# SCH_Wordy-Watch-V1_1_2026-04-09.net
KiCad netlist of a schematic drawn in EasyEDA
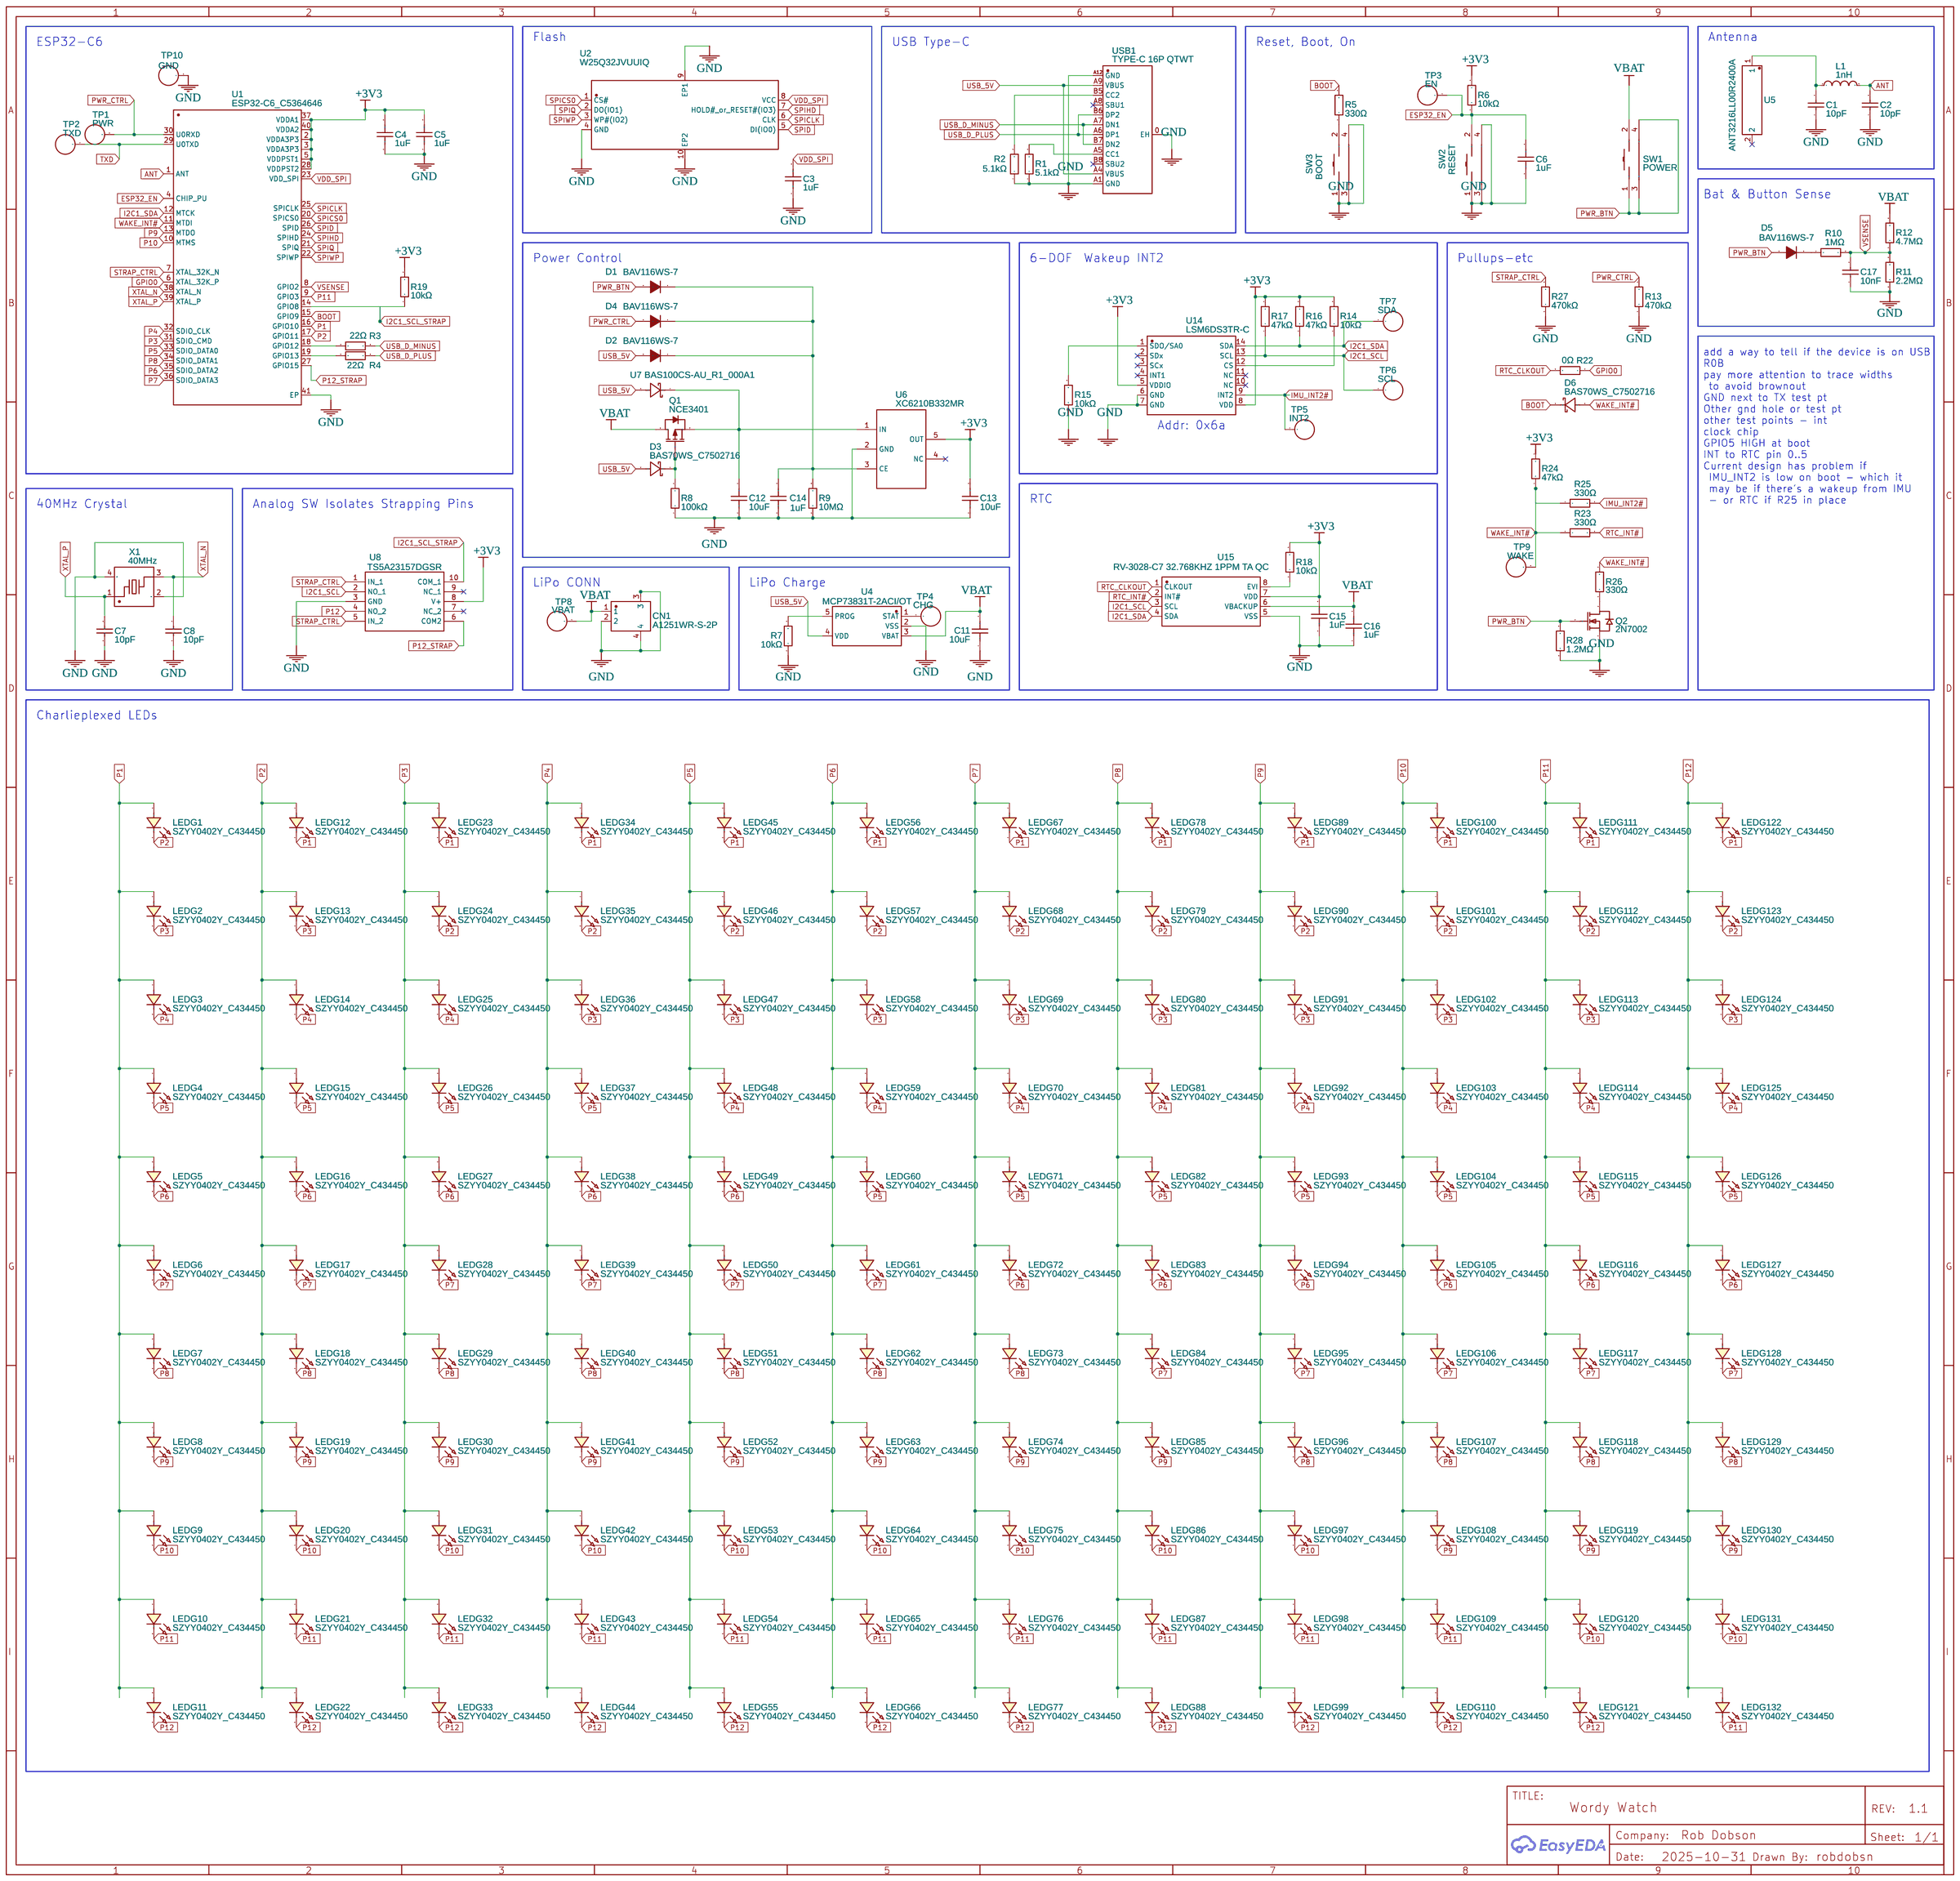
[diagram p0: schematic sheet]

(export (version "E")
  (design (tool "Eeschema 10.0.6"))
  (components
    (comp (ref "C1")
      (value "10pF")
      (fields
        (field (name "Manufacturer Part") "CL10C100JB8NNNC")
        (field (name "Manufacturer") "SAMSUNG(三星)")
      )
      (libsource (lib "") (part "CL10C100JB8NNNC"))
    )
    (comp (ref "C2")
      (value "10pF")
      (fields
        (field (name "Manufacturer Part") "CL10C100JB8NNNC")
        (field (name "Manufacturer") "SAMSUNG(三星)")
      )
      (libsource (lib "") (part "CL10C100JB8NNNC"))
    )
    (comp (ref "C3")
      (value "1uF")
      (fields
        (field (name "Manufacturer Part") "CL10A105KB8NNNC")
        (field (name "Manufacturer") "SAMSUNG(三星)")
      )
      (libsource (lib "") (part "CL10A105KB8NNNC"))
    )
    (comp (ref "C4")
      (value "1uF")
      (fields
        (field (name "Manufacturer Part") "CL10A105KB8NNNC")
        (field (name "Manufacturer") "SAMSUNG(三星)")
      )
      (libsource (lib "") (part "CL10A105KB8NNNC"))
    )
    (comp (ref "C5")
      (value "1uF")
      (fields
        (field (name "Manufacturer Part") "CL10A105KB8NNNC")
        (field (name "Manufacturer") "SAMSUNG(三星)")
      )
      (libsource (lib "") (part "CL10A105KB8NNNC"))
    )
    (comp (ref "C6")
      (value "1uF")
      (fields
        (field (name "Manufacturer Part") "CL10A105KB8NNNC")
        (field (name "Manufacturer") "SAMSUNG(三星)")
      )
      (libsource (lib "") (part "CL10A105KB8NNNC"))
    )
    (comp (ref "C7")
      (value "10pF")
      (fields
        (field (name "Manufacturer Part") "CL10C100JB8NNNC")
        (field (name "Manufacturer") "SAMSUNG(三星)")
      )
      (libsource (lib "") (part "CL10C100JB8NNNC"))
    )
    (comp (ref "C8")
      (value "10pF")
      (fields
        (field (name "Manufacturer Part") "CL10C100JB8NNNC")
        (field (name "Manufacturer") "SAMSUNG(三星)")
      )
      (libsource (lib "") (part "CL10C100JB8NNNC"))
    )
    (comp (ref "C11")
      (value "10uF")
      (fields
        (field (name "Manufacturer Part") "CL10A106MA8NRNC")
        (field (name "Manufacturer") "SAMSUNG(三星)")
      )
      (libsource (lib "") (part "CL10A106MA8NRNC"))
    )
    (comp (ref "C12")
      (value "10uF")
      (fields
        (field (name "Manufacturer Part") "CL10A106MA8NRNC")
        (field (name "Manufacturer") "SAMSUNG(三星)")
      )
      (libsource (lib "") (part "CL10A106MA8NRNC_1"))
    )
    (comp (ref "C13")
      (value "10uF")
      (fields
        (field (name "Manufacturer Part") "CL10A106MA8NRNC")
        (field (name "Manufacturer") "SAMSUNG(三星)")
      )
      (libsource (lib "") (part "CL10A106MA8NRNC_1"))
    )
    (comp (ref "C14")
      (value "1uF")
      (fields
        (field (name "Manufacturer Part") "CL10A105KB8NNNC")
        (field (name "Manufacturer") "SAMSUNG(三星)")
      )
      (libsource (lib "") (part "CL10A105KB8NNNC"))
    )
    (comp (ref "C15")
      (value "1uF")
      (fields
        (field (name "Manufacturer Part") "CL10A105KB8NNNC")
        (field (name "Manufacturer") "SAMSUNG(三星)")
      )
      (libsource (lib "") (part "CL10A105KB8NNNC"))
    )
    (comp (ref "C16")
      (value "1uF")
      (fields
        (field (name "Manufacturer Part") "CL10A105KB8NNNC")
        (field (name "Manufacturer") "SAMSUNG(三星)")
      )
      (libsource (lib "") (part "CL10A105KB8NNNC"))
    )
    (comp (ref "C17")
      (value "10nF")
      (fields (field (name "Manufacturer Part") "0603B103K500NT") (field (name "Manufacturer") "FH(风华)"))
      (libsource (lib "") (part "0603B103K500NT"))
    )
    (comp (ref "CN1")
      (value "A1251WR-S-2P")
      (fields (field (name "Manufacturer") "CJT(长江连接器)"))
      (libsource (lib "") (part "A1251WR-S-2P"))
    )
    (comp (ref "D1")
      (value "BAV116WS-7")
      (fields (field (name "Manufacturer") "DIODES(美台)"))
      (libsource (lib "") (part "BAV116WS-7"))
    )
    (comp (ref "D2")
      (value "BAV116WS-7")
      (fields (field (name "Manufacturer") "DIODES(美台)"))
      (libsource (lib "") (part "BAV116WS-7"))
    )
    (comp (ref "D3")
      (value "BAS70WS_C7502716")
      (fields (field (name "Manufacturer Part") "BAS70WS") (field (name "Manufacturer") "R+O(宏嘉诚)"))
      (libsource (lib "") (part "BAS70WS_C7502716_1"))
    )
    (comp (ref "D4")
      (value "BAV116WS-7")
      (fields (field (name "Manufacturer") "DIODES(美台)"))
      (libsource (lib "") (part "BAV116WS-7"))
    )
    (comp (ref "D5")
      (value "BAV116WS-7")
      (fields (field (name "Manufacturer") "DIODES(美台)"))
      (libsource (lib "") (part "BAV116WS-7"))
    )
    (comp (ref "D6")
      (value "BAS70WS_C7502716")
      (fields (field (name "Manufacturer Part") "BAS70WS") (field (name "Manufacturer") "R+O(宏嘉诚)"))
      (libsource (lib "") (part "BAS70WS_C7502716"))
    )
    (comp (ref "L1")
      (value "1nH")
      (fields (field (name "Manufacturer Part") "LQG15HS1N0S02D") (field (name "Manufacturer") "muRata(村田)"))
      (libsource (lib "") (part "LQG15HS1N0S02D"))
    )
    (comp (ref "LEDG1")
      (value "SZYY0402Y_C434450")
      (fields (field (name "Manufacturer Part") "SZYY0402Y") (field (name "Manufacturer") "yongyu(永裕光电)"))
      (libsource (lib "") (part "SZYY0402Y_C434450"))
    )
    (comp (ref "LEDG2")
      (value "SZYY0402Y_C434450")
      (fields (field (name "Manufacturer Part") "SZYY0402Y") (field (name "Manufacturer") "yongyu(永裕光电)"))
      (libsource (lib "") (part "SZYY0402Y_C434450"))
    )
    (comp (ref "LEDG3")
      (value "SZYY0402Y_C434450")
      (fields (field (name "Manufacturer Part") "SZYY0402Y") (field (name "Manufacturer") "yongyu(永裕光电)"))
      (libsource (lib "") (part "SZYY0402Y_C434450"))
    )
    (comp (ref "LEDG4")
      (value "SZYY0402Y_C434450")
      (fields (field (name "Manufacturer Part") "SZYY0402Y") (field (name "Manufacturer") "yongyu(永裕光电)"))
      (libsource (lib "") (part "SZYY0402Y_C434450"))
    )
    (comp (ref "LEDG5")
      (value "SZYY0402Y_C434450")
      (fields (field (name "Manufacturer Part") "SZYY0402Y") (field (name "Manufacturer") "yongyu(永裕光电)"))
      (libsource (lib "") (part "SZYY0402Y_C434450"))
    )
    (comp (ref "LEDG6")
      (value "SZYY0402Y_C434450")
      (fields (field (name "Manufacturer Part") "SZYY0402Y") (field (name "Manufacturer") "yongyu(永裕光电)"))
      (libsource (lib "") (part "SZYY0402Y_C434450"))
    )
    (comp (ref "LEDG7")
      (value "SZYY0402Y_C434450")
      (fields (field (name "Manufacturer Part") "SZYY0402Y") (field (name "Manufacturer") "yongyu(永裕光电)"))
      (libsource (lib "") (part "SZYY0402Y_C434450"))
    )
    (comp (ref "LEDG8")
      (value "SZYY0402Y_C434450")
      (fields (field (name "Manufacturer Part") "SZYY0402Y") (field (name "Manufacturer") "yongyu(永裕光电)"))
      (libsource (lib "") (part "SZYY0402Y_C434450"))
    )
    (comp (ref "LEDG9")
      (value "SZYY0402Y_C434450")
      (fields (field (name "Manufacturer Part") "SZYY0402Y") (field (name "Manufacturer") "yongyu(永裕光电)"))
      (libsource (lib "") (part "SZYY0402Y_C434450"))
    )
    (comp (ref "LEDG10")
      (value "SZYY0402Y_C434450")
      (fields (field (name "Manufacturer Part") "SZYY0402Y") (field (name "Manufacturer") "yongyu(永裕光电)"))
      (libsource (lib "") (part "SZYY0402Y_C434450"))
    )
    (comp (ref "LEDG11")
      (value "SZYY0402Y_C434450")
      (fields (field (name "Manufacturer Part") "SZYY0402Y") (field (name "Manufacturer") "yongyu(永裕光电)"))
      (libsource (lib "") (part "SZYY0402Y_C434450"))
    )
    (comp (ref "LEDG12")
      (value "SZYY0402Y_C434450")
      (fields (field (name "Manufacturer Part") "SZYY0402Y") (field (name "Manufacturer") "yongyu(永裕光电)"))
      (libsource (lib "") (part "SZYY0402Y_C434450"))
    )
    (comp (ref "LEDG13")
      (value "SZYY0402Y_C434450")
      (fields (field (name "Manufacturer Part") "SZYY0402Y") (field (name "Manufacturer") "yongyu(永裕光电)"))
      (libsource (lib "") (part "SZYY0402Y_C434450"))
    )
    (comp (ref "LEDG14")
      (value "SZYY0402Y_C434450")
      (fields (field (name "Manufacturer Part") "SZYY0402Y") (field (name "Manufacturer") "yongyu(永裕光电)"))
      (libsource (lib "") (part "SZYY0402Y_C434450"))
    )
    (comp (ref "LEDG15")
      (value "SZYY0402Y_C434450")
      (fields (field (name "Manufacturer Part") "SZYY0402Y") (field (name "Manufacturer") "yongyu(永裕光电)"))
      (libsource (lib "") (part "SZYY0402Y_C434450"))
    )
    (comp (ref "LEDG16")
      (value "SZYY0402Y_C434450")
      (fields (field (name "Manufacturer Part") "SZYY0402Y") (field (name "Manufacturer") "yongyu(永裕光电)"))
      (libsource (lib "") (part "SZYY0402Y_C434450"))
    )
    (comp (ref "LEDG17")
      (value "SZYY0402Y_C434450")
      (fields (field (name "Manufacturer Part") "SZYY0402Y") (field (name "Manufacturer") "yongyu(永裕光电)"))
      (libsource (lib "") (part "SZYY0402Y_C434450"))
    )
    (comp (ref "LEDG18")
      (value "SZYY0402Y_C434450")
      (fields (field (name "Manufacturer Part") "SZYY0402Y") (field (name "Manufacturer") "yongyu(永裕光电)"))
      (libsource (lib "") (part "SZYY0402Y_C434450"))
    )
    (comp (ref "LEDG19")
      (value "SZYY0402Y_C434450")
      (fields (field (name "Manufacturer Part") "SZYY0402Y") (field (name "Manufacturer") "yongyu(永裕光电)"))
      (libsource (lib "") (part "SZYY0402Y_C434450"))
    )
    (comp (ref "LEDG20")
      (value "SZYY0402Y_C434450")
      (fields (field (name "Manufacturer Part") "SZYY0402Y") (field (name "Manufacturer") "yongyu(永裕光电)"))
      (libsource (lib "") (part "SZYY0402Y_C434450"))
    )
    (comp (ref "LEDG21")
      (value "SZYY0402Y_C434450")
      (fields (field (name "Manufacturer Part") "SZYY0402Y") (field (name "Manufacturer") "yongyu(永裕光电)"))
      (libsource (lib "") (part "SZYY0402Y_C434450"))
    )
    (comp (ref "LEDG22")
      (value "SZYY0402Y_C434450")
      (fields (field (name "Manufacturer Part") "SZYY0402Y") (field (name "Manufacturer") "yongyu(永裕光电)"))
      (libsource (lib "") (part "SZYY0402Y_C434450"))
    )
    (comp (ref "LEDG23")
      (value "SZYY0402Y_C434450")
      (fields (field (name "Manufacturer Part") "SZYY0402Y") (field (name "Manufacturer") "yongyu(永裕光电)"))
      (libsource (lib "") (part "SZYY0402Y_C434450"))
    )
    (comp (ref "LEDG24")
      (value "SZYY0402Y_C434450")
      (fields (field (name "Manufacturer Part") "SZYY0402Y") (field (name "Manufacturer") "yongyu(永裕光电)"))
      (libsource (lib "") (part "SZYY0402Y_C434450"))
    )
    (comp (ref "LEDG25")
      (value "SZYY0402Y_C434450")
      (fields (field (name "Manufacturer Part") "SZYY0402Y") (field (name "Manufacturer") "yongyu(永裕光电)"))
      (libsource (lib "") (part "SZYY0402Y_C434450"))
    )
    (comp (ref "LEDG26")
      (value "SZYY0402Y_C434450")
      (fields (field (name "Manufacturer Part") "SZYY0402Y") (field (name "Manufacturer") "yongyu(永裕光电)"))
      (libsource (lib "") (part "SZYY0402Y_C434450"))
    )
    (comp (ref "LEDG27")
      (value "SZYY0402Y_C434450")
      (fields (field (name "Manufacturer Part") "SZYY0402Y") (field (name "Manufacturer") "yongyu(永裕光电)"))
      (libsource (lib "") (part "SZYY0402Y_C434450"))
    )
    (comp (ref "LEDG28")
      (value "SZYY0402Y_C434450")
      (fields (field (name "Manufacturer Part") "SZYY0402Y") (field (name "Manufacturer") "yongyu(永裕光电)"))
      (libsource (lib "") (part "SZYY0402Y_C434450"))
    )
    (comp (ref "LEDG29")
      (value "SZYY0402Y_C434450")
      (fields (field (name "Manufacturer Part") "SZYY0402Y") (field (name "Manufacturer") "yongyu(永裕光电)"))
      (libsource (lib "") (part "SZYY0402Y_C434450"))
    )
    (comp (ref "LEDG30")
      (value "SZYY0402Y_C434450")
      (fields (field (name "Manufacturer Part") "SZYY0402Y") (field (name "Manufacturer") "yongyu(永裕光电)"))
      (libsource (lib "") (part "SZYY0402Y_C434450"))
    )
    (comp (ref "LEDG31")
      (value "SZYY0402Y_C434450")
      (fields (field (name "Manufacturer Part") "SZYY0402Y") (field (name "Manufacturer") "yongyu(永裕光电)"))
      (libsource (lib "") (part "SZYY0402Y_C434450"))
    )
    (comp (ref "LEDG32")
      (value "SZYY0402Y_C434450")
      (fields (field (name "Manufacturer Part") "SZYY0402Y") (field (name "Manufacturer") "yongyu(永裕光电)"))
      (libsource (lib "") (part "SZYY0402Y_C434450"))
    )
    (comp (ref "LEDG33")
      (value "SZYY0402Y_C434450")
      (fields (field (name "Manufacturer Part") "SZYY0402Y") (field (name "Manufacturer") "yongyu(永裕光电)"))
      (libsource (lib "") (part "SZYY0402Y_C434450"))
    )
    (comp (ref "LEDG34")
      (value "SZYY0402Y_C434450")
      (fields (field (name "Manufacturer Part") "SZYY0402Y") (field (name "Manufacturer") "yongyu(永裕光电)"))
      (libsource (lib "") (part "SZYY0402Y_C434450"))
    )
    (comp (ref "LEDG35")
      (value "SZYY0402Y_C434450")
      (fields (field (name "Manufacturer Part") "SZYY0402Y") (field (name "Manufacturer") "yongyu(永裕光电)"))
      (libsource (lib "") (part "SZYY0402Y_C434450"))
    )
    (comp (ref "LEDG36")
      (value "SZYY0402Y_C434450")
      (fields (field (name "Manufacturer Part") "SZYY0402Y") (field (name "Manufacturer") "yongyu(永裕光电)"))
      (libsource (lib "") (part "SZYY0402Y_C434450"))
    )
    (comp (ref "LEDG37")
      (value "SZYY0402Y_C434450")
      (fields (field (name "Manufacturer Part") "SZYY0402Y") (field (name "Manufacturer") "yongyu(永裕光电)"))
      (libsource (lib "") (part "SZYY0402Y_C434450"))
    )
    (comp (ref "LEDG38")
      (value "SZYY0402Y_C434450")
      (fields (field (name "Manufacturer Part") "SZYY0402Y") (field (name "Manufacturer") "yongyu(永裕光电)"))
      (libsource (lib "") (part "SZYY0402Y_C434450"))
    )
    (comp (ref "LEDG39")
      (value "SZYY0402Y_C434450")
      (fields (field (name "Manufacturer Part") "SZYY0402Y") (field (name "Manufacturer") "yongyu(永裕光电)"))
      (libsource (lib "") (part "SZYY0402Y_C434450"))
    )
    (comp (ref "LEDG40")
      (value "SZYY0402Y_C434450")
      (fields (field (name "Manufacturer Part") "SZYY0402Y") (field (name "Manufacturer") "yongyu(永裕光电)"))
      (libsource (lib "") (part "SZYY0402Y_C434450"))
    )
    (comp (ref "LEDG41")
      (value "SZYY0402Y_C434450")
      (fields (field (name "Manufacturer Part") "SZYY0402Y") (field (name "Manufacturer") "yongyu(永裕光电)"))
      (libsource (lib "") (part "SZYY0402Y_C434450"))
    )
    (comp (ref "LEDG42")
      (value "SZYY0402Y_C434450")
      (fields (field (name "Manufacturer Part") "SZYY0402Y") (field (name "Manufacturer") "yongyu(永裕光电)"))
      (libsource (lib "") (part "SZYY0402Y_C434450"))
    )
    (comp (ref "LEDG43")
      (value "SZYY0402Y_C434450")
      (fields (field (name "Manufacturer Part") "SZYY0402Y") (field (name "Manufacturer") "yongyu(永裕光电)"))
      (libsource (lib "") (part "SZYY0402Y_C434450"))
    )
    (comp (ref "LEDG44")
      (value "SZYY0402Y_C434450")
      (fields (field (name "Manufacturer Part") "SZYY0402Y") (field (name "Manufacturer") "yongyu(永裕光电)"))
      (libsource (lib "") (part "SZYY0402Y_C434450"))
    )
    (comp (ref "LEDG45")
      (value "SZYY0402Y_C434450")
      (fields (field (name "Manufacturer Part") "SZYY0402Y") (field (name "Manufacturer") "yongyu(永裕光电)"))
      (libsource (lib "") (part "SZYY0402Y_C434450"))
    )
    (comp (ref "LEDG46")
      (value "SZYY0402Y_C434450")
      (fields (field (name "Manufacturer Part") "SZYY0402Y") (field (name "Manufacturer") "yongyu(永裕光电)"))
      (libsource (lib "") (part "SZYY0402Y_C434450"))
    )
    (comp (ref "LEDG47")
      (value "SZYY0402Y_C434450")
      (fields (field (name "Manufacturer Part") "SZYY0402Y") (field (name "Manufacturer") "yongyu(永裕光电)"))
      (libsource (lib "") (part "SZYY0402Y_C434450"))
    )
    (comp (ref "LEDG48")
      (value "SZYY0402Y_C434450")
      (fields (field (name "Manufacturer Part") "SZYY0402Y") (field (name "Manufacturer") "yongyu(永裕光电)"))
      (libsource (lib "") (part "SZYY0402Y_C434450"))
    )
    (comp (ref "LEDG49")
      (value "SZYY0402Y_C434450")
      (fields (field (name "Manufacturer Part") "SZYY0402Y") (field (name "Manufacturer") "yongyu(永裕光电)"))
      (libsource (lib "") (part "SZYY0402Y_C434450"))
    )
    (comp (ref "LEDG50")
      (value "SZYY0402Y_C434450")
      (fields (field (name "Manufacturer Part") "SZYY0402Y") (field (name "Manufacturer") "yongyu(永裕光电)"))
      (libsource (lib "") (part "SZYY0402Y_C434450"))
    )
    (comp (ref "LEDG51")
      (value "SZYY0402Y_C434450")
      (fields (field (name "Manufacturer Part") "SZYY0402Y") (field (name "Manufacturer") "yongyu(永裕光电)"))
      (libsource (lib "") (part "SZYY0402Y_C434450"))
    )
    (comp (ref "LEDG52")
      (value "SZYY0402Y_C434450")
      (fields (field (name "Manufacturer Part") "SZYY0402Y") (field (name "Manufacturer") "yongyu(永裕光电)"))
      (libsource (lib "") (part "SZYY0402Y_C434450"))
    )
    (comp (ref "LEDG53")
      (value "SZYY0402Y_C434450")
      (fields (field (name "Manufacturer Part") "SZYY0402Y") (field (name "Manufacturer") "yongyu(永裕光电)"))
      (libsource (lib "") (part "SZYY0402Y_C434450"))
    )
    (comp (ref "LEDG54")
      (value "SZYY0402Y_C434450")
      (fields (field (name "Manufacturer Part") "SZYY0402Y") (field (name "Manufacturer") "yongyu(永裕光电)"))
      (libsource (lib "") (part "SZYY0402Y_C434450"))
    )
    (comp (ref "LEDG55")
      (value "SZYY0402Y_C434450")
      (fields (field (name "Manufacturer Part") "SZYY0402Y") (field (name "Manufacturer") "yongyu(永裕光电)"))
      (libsource (lib "") (part "SZYY0402Y_C434450"))
    )
    (comp (ref "LEDG56")
      (value "SZYY0402Y_C434450")
      (fields (field (name "Manufacturer Part") "SZYY0402Y") (field (name "Manufacturer") "yongyu(永裕光电)"))
      (libsource (lib "") (part "SZYY0402Y_C434450"))
    )
    (comp (ref "LEDG57")
      (value "SZYY0402Y_C434450")
      (fields (field (name "Manufacturer Part") "SZYY0402Y") (field (name "Manufacturer") "yongyu(永裕光电)"))
      (libsource (lib "") (part "SZYY0402Y_C434450"))
    )
    (comp (ref "LEDG58")
      (value "SZYY0402Y_C434450")
      (fields (field (name "Manufacturer Part") "SZYY0402Y") (field (name "Manufacturer") "yongyu(永裕光电)"))
      (libsource (lib "") (part "SZYY0402Y_C434450"))
    )
    (comp (ref "LEDG59")
      (value "SZYY0402Y_C434450")
      (fields (field (name "Manufacturer Part") "SZYY0402Y") (field (name "Manufacturer") "yongyu(永裕光电)"))
      (libsource (lib "") (part "SZYY0402Y_C434450"))
    )
    (comp (ref "LEDG60")
      (value "SZYY0402Y_C434450")
      (fields (field (name "Manufacturer Part") "SZYY0402Y") (field (name "Manufacturer") "yongyu(永裕光电)"))
      (libsource (lib "") (part "SZYY0402Y_C434450"))
    )
    (comp (ref "LEDG61")
      (value "SZYY0402Y_C434450")
      (fields (field (name "Manufacturer Part") "SZYY0402Y") (field (name "Manufacturer") "yongyu(永裕光电)"))
      (libsource (lib "") (part "SZYY0402Y_C434450"))
    )
    (comp (ref "LEDG62")
      (value "SZYY0402Y_C434450")
      (fields (field (name "Manufacturer Part") "SZYY0402Y") (field (name "Manufacturer") "yongyu(永裕光电)"))
      (libsource (lib "") (part "SZYY0402Y_C434450"))
    )
    (comp (ref "LEDG63")
      (value "SZYY0402Y_C434450")
      (fields (field (name "Manufacturer Part") "SZYY0402Y") (field (name "Manufacturer") "yongyu(永裕光电)"))
      (libsource (lib "") (part "SZYY0402Y_C434450"))
    )
    (comp (ref "LEDG64")
      (value "SZYY0402Y_C434450")
      (fields (field (name "Manufacturer Part") "SZYY0402Y") (field (name "Manufacturer") "yongyu(永裕光电)"))
      (libsource (lib "") (part "SZYY0402Y_C434450"))
    )
    (comp (ref "LEDG65")
      (value "SZYY0402Y_C434450")
      (fields (field (name "Manufacturer Part") "SZYY0402Y") (field (name "Manufacturer") "yongyu(永裕光电)"))
      (libsource (lib "") (part "SZYY0402Y_C434450"))
    )
    (comp (ref "LEDG66")
      (value "SZYY0402Y_C434450")
      (fields (field (name "Manufacturer Part") "SZYY0402Y") (field (name "Manufacturer") "yongyu(永裕光电)"))
      (libsource (lib "") (part "SZYY0402Y_C434450"))
    )
    (comp (ref "LEDG67")
      (value "SZYY0402Y_C434450")
      (fields (field (name "Manufacturer Part") "SZYY0402Y") (field (name "Manufacturer") "yongyu(永裕光电)"))
      (libsource (lib "") (part "SZYY0402Y_C434450"))
    )
    (comp (ref "LEDG68")
      (value "SZYY0402Y_C434450")
      (fields (field (name "Manufacturer Part") "SZYY0402Y") (field (name "Manufacturer") "yongyu(永裕光电)"))
      (libsource (lib "") (part "SZYY0402Y_C434450"))
    )
    (comp (ref "LEDG69")
      (value "SZYY0402Y_C434450")
      (fields (field (name "Manufacturer Part") "SZYY0402Y") (field (name "Manufacturer") "yongyu(永裕光电)"))
      (libsource (lib "") (part "SZYY0402Y_C434450"))
    )
    (comp (ref "LEDG70")
      (value "SZYY0402Y_C434450")
      (fields (field (name "Manufacturer Part") "SZYY0402Y") (field (name "Manufacturer") "yongyu(永裕光电)"))
      (libsource (lib "") (part "SZYY0402Y_C434450"))
    )
    (comp (ref "LEDG71")
      (value "SZYY0402Y_C434450")
      (fields (field (name "Manufacturer Part") "SZYY0402Y") (field (name "Manufacturer") "yongyu(永裕光电)"))
      (libsource (lib "") (part "SZYY0402Y_C434450"))
    )
    (comp (ref "LEDG72")
      (value "SZYY0402Y_C434450")
      (fields (field (name "Manufacturer Part") "SZYY0402Y") (field (name "Manufacturer") "yongyu(永裕光电)"))
      (libsource (lib "") (part "SZYY0402Y_C434450"))
    )
    (comp (ref "LEDG73")
      (value "SZYY0402Y_C434450")
      (fields (field (name "Manufacturer Part") "SZYY0402Y") (field (name "Manufacturer") "yongyu(永裕光电)"))
      (libsource (lib "") (part "SZYY0402Y_C434450"))
    )
    (comp (ref "LEDG74")
      (value "SZYY0402Y_C434450")
      (fields (field (name "Manufacturer Part") "SZYY0402Y") (field (name "Manufacturer") "yongyu(永裕光电)"))
      (libsource (lib "") (part "SZYY0402Y_C434450"))
    )
    (comp (ref "LEDG75")
      (value "SZYY0402Y_C434450")
      (fields (field (name "Manufacturer Part") "SZYY0402Y") (field (name "Manufacturer") "yongyu(永裕光电)"))
      (libsource (lib "") (part "SZYY0402Y_C434450"))
    )
    (comp (ref "LEDG76")
      (value "SZYY0402Y_C434450")
      (fields (field (name "Manufacturer Part") "SZYY0402Y") (field (name "Manufacturer") "yongyu(永裕光电)"))
      (libsource (lib "") (part "SZYY0402Y_C434450"))
    )
    (comp (ref "LEDG77")
      (value "SZYY0402Y_C434450")
      (fields (field (name "Manufacturer Part") "SZYY0402Y") (field (name "Manufacturer") "yongyu(永裕光电)"))
      (libsource (lib "") (part "SZYY0402Y_C434450"))
    )
    (comp (ref "LEDG78")
      (value "SZYY0402Y_C434450")
      (fields (field (name "Manufacturer Part") "SZYY0402Y") (field (name "Manufacturer") "yongyu(永裕光电)"))
      (libsource (lib "") (part "SZYY0402Y_C434450"))
    )
    (comp (ref "LEDG79")
      (value "SZYY0402Y_C434450")
      (fields (field (name "Manufacturer Part") "SZYY0402Y") (field (name "Manufacturer") "yongyu(永裕光电)"))
      (libsource (lib "") (part "SZYY0402Y_C434450"))
    )
    (comp (ref "LEDG80")
      (value "SZYY0402Y_C434450")
      (fields (field (name "Manufacturer Part") "SZYY0402Y") (field (name "Manufacturer") "yongyu(永裕光电)"))
      (libsource (lib "") (part "SZYY0402Y_C434450"))
    )
    (comp (ref "LEDG81")
      (value "SZYY0402Y_C434450")
      (fields (field (name "Manufacturer Part") "SZYY0402Y") (field (name "Manufacturer") "yongyu(永裕光电)"))
      (libsource (lib "") (part "SZYY0402Y_C434450"))
    )
    (comp (ref "LEDG82")
      (value "SZYY0402Y_C434450")
      (fields (field (name "Manufacturer Part") "SZYY0402Y") (field (name "Manufacturer") "yongyu(永裕光电)"))
      (libsource (lib "") (part "SZYY0402Y_C434450"))
    )
    (comp (ref "LEDG83")
      (value "SZYY0402Y_C434450")
      (fields (field (name "Manufacturer Part") "SZYY0402Y") (field (name "Manufacturer") "yongyu(永裕光电)"))
      (libsource (lib "") (part "SZYY0402Y_C434450"))
    )
    (comp (ref "LEDG84")
      (value "SZYY0402Y_C434450")
      (fields (field (name "Manufacturer Part") "SZYY0402Y") (field (name "Manufacturer") "yongyu(永裕光电)"))
      (libsource (lib "") (part "SZYY0402Y_C434450"))
    )
    (comp (ref "LEDG85")
      (value "SZYY0402Y_C434450")
      (fields (field (name "Manufacturer Part") "SZYY0402Y") (field (name "Manufacturer") "yongyu(永裕光电)"))
      (libsource (lib "") (part "SZYY0402Y_C434450"))
    )
    (comp (ref "LEDG86")
      (value "SZYY0402Y_C434450")
      (fields (field (name "Manufacturer Part") "SZYY0402Y") (field (name "Manufacturer") "yongyu(永裕光电)"))
      (libsource (lib "") (part "SZYY0402Y_C434450"))
    )
    (comp (ref "LEDG87")
      (value "SZYY0402Y_C434450")
      (fields (field (name "Manufacturer Part") "SZYY0402Y") (field (name "Manufacturer") "yongyu(永裕光电)"))
      (libsource (lib "") (part "SZYY0402Y_C434450"))
    )
    (comp (ref "LEDG88")
      (value "SZYY0402Y_C434450")
      (fields (field (name "Manufacturer Part") "SZYY0402Y") (field (name "Manufacturer") "yongyu(永裕光电)"))
      (libsource (lib "") (part "SZYY0402Y_C434450"))
    )
    (comp (ref "LEDG89")
      (value "SZYY0402Y_C434450")
      (fields (field (name "Manufacturer Part") "SZYY0402Y") (field (name "Manufacturer") "yongyu(永裕光电)"))
      (libsource (lib "") (part "SZYY0402Y_C434450"))
    )
    (comp (ref "LEDG90")
      (value "SZYY0402Y_C434450")
      (fields (field (name "Manufacturer Part") "SZYY0402Y") (field (name "Manufacturer") "yongyu(永裕光电)"))
      (libsource (lib "") (part "SZYY0402Y_C434450"))
    )
    (comp (ref "LEDG91")
      (value "SZYY0402Y_C434450")
      (fields (field (name "Manufacturer Part") "SZYY0402Y") (field (name "Manufacturer") "yongyu(永裕光电)"))
      (libsource (lib "") (part "SZYY0402Y_C434450"))
    )
    (comp (ref "LEDG92")
      (value "SZYY0402Y_C434450")
      (fields (field (name "Manufacturer Part") "SZYY0402Y") (field (name "Manufacturer") "yongyu(永裕光电)"))
      (libsource (lib "") (part "SZYY0402Y_C434450"))
    )
    (comp (ref "LEDG93")
      (value "SZYY0402Y_C434450")
      (fields (field (name "Manufacturer Part") "SZYY0402Y") (field (name "Manufacturer") "yongyu(永裕光电)"))
      (libsource (lib "") (part "SZYY0402Y_C434450"))
    )
    (comp (ref "LEDG94")
      (value "SZYY0402Y_C434450")
      (fields (field (name "Manufacturer Part") "SZYY0402Y") (field (name "Manufacturer") "yongyu(永裕光电)"))
      (libsource (lib "") (part "SZYY0402Y_C434450"))
    )
    (comp (ref "LEDG95")
      (value "SZYY0402Y_C434450")
      (fields (field (name "Manufacturer Part") "SZYY0402Y") (field (name "Manufacturer") "yongyu(永裕光电)"))
      (libsource (lib "") (part "SZYY0402Y_C434450"))
    )
    (comp (ref "LEDG96")
      (value "SZYY0402Y_C434450")
      (fields (field (name "Manufacturer Part") "SZYY0402Y") (field (name "Manufacturer") "yongyu(永裕光电)"))
      (libsource (lib "") (part "SZYY0402Y_C434450"))
    )
    (comp (ref "LEDG97")
      (value "SZYY0402Y_C434450")
      (fields (field (name "Manufacturer Part") "SZYY0402Y") (field (name "Manufacturer") "yongyu(永裕光电)"))
      (libsource (lib "") (part "SZYY0402Y_C434450"))
    )
    (comp (ref "LEDG98")
      (value "SZYY0402Y_C434450")
      (fields (field (name "Manufacturer Part") "SZYY0402Y") (field (name "Manufacturer") "yongyu(永裕光电)"))
      (libsource (lib "") (part "SZYY0402Y_C434450"))
    )
    (comp (ref "LEDG99")
      (value "SZYY0402Y_C434450")
      (fields (field (name "Manufacturer Part") "SZYY0402Y") (field (name "Manufacturer") "yongyu(永裕光电)"))
      (libsource (lib "") (part "SZYY0402Y_C434450"))
    )
    (comp (ref "LEDG100")
      (value "SZYY0402Y_C434450")
      (fields (field (name "Manufacturer Part") "SZYY0402Y") (field (name "Manufacturer") "yongyu(永裕光电)"))
      (libsource (lib "") (part "SZYY0402Y_C434450"))
    )
    (comp (ref "LEDG101")
      (value "SZYY0402Y_C434450")
      (fields (field (name "Manufacturer Part") "SZYY0402Y") (field (name "Manufacturer") "yongyu(永裕光电)"))
      (libsource (lib "") (part "SZYY0402Y_C434450"))
    )
    (comp (ref "LEDG102")
      (value "SZYY0402Y_C434450")
      (fields (field (name "Manufacturer Part") "SZYY0402Y") (field (name "Manufacturer") "yongyu(永裕光电)"))
      (libsource (lib "") (part "SZYY0402Y_C434450"))
    )
    (comp (ref "LEDG103")
      (value "SZYY0402Y_C434450")
      (fields (field (name "Manufacturer Part") "SZYY0402Y") (field (name "Manufacturer") "yongyu(永裕光电)"))
      (libsource (lib "") (part "SZYY0402Y_C434450"))
    )
    (comp (ref "LEDG104")
      (value "SZYY0402Y_C434450")
      (fields (field (name "Manufacturer Part") "SZYY0402Y") (field (name "Manufacturer") "yongyu(永裕光电)"))
      (libsource (lib "") (part "SZYY0402Y_C434450"))
    )
    (comp (ref "LEDG105")
      (value "SZYY0402Y_C434450")
      (fields (field (name "Manufacturer Part") "SZYY0402Y") (field (name "Manufacturer") "yongyu(永裕光电)"))
      (libsource (lib "") (part "SZYY0402Y_C434450"))
    )
    (comp (ref "LEDG106")
      (value "SZYY0402Y_C434450")
      (fields (field (name "Manufacturer Part") "SZYY0402Y") (field (name "Manufacturer") "yongyu(永裕光电)"))
      (libsource (lib "") (part "SZYY0402Y_C434450"))
    )
    (comp (ref "LEDG107")
      (value "SZYY0402Y_C434450")
      (fields (field (name "Manufacturer Part") "SZYY0402Y") (field (name "Manufacturer") "yongyu(永裕光电)"))
      (libsource (lib "") (part "SZYY0402Y_C434450"))
    )
    (comp (ref "LEDG108")
      (value "SZYY0402Y_C434450")
      (fields (field (name "Manufacturer Part") "SZYY0402Y") (field (name "Manufacturer") "yongyu(永裕光电)"))
      (libsource (lib "") (part "SZYY0402Y_C434450"))
    )
    (comp (ref "LEDG109")
      (value "SZYY0402Y_C434450")
      (fields (field (name "Manufacturer Part") "SZYY0402Y") (field (name "Manufacturer") "yongyu(永裕光电)"))
      (libsource (lib "") (part "SZYY0402Y_C434450"))
    )
    (comp (ref "LEDG110")
      (value "SZYY0402Y_C434450")
      (fields (field (name "Manufacturer Part") "SZYY0402Y") (field (name "Manufacturer") "yongyu(永裕光电)"))
      (libsource (lib "") (part "SZYY0402Y_C434450"))
    )
    (comp (ref "LEDG111")
      (value "SZYY0402Y_C434450")
      (fields (field (name "Manufacturer Part") "SZYY0402Y") (field (name "Manufacturer") "yongyu(永裕光电)"))
      (libsource (lib "") (part "SZYY0402Y_C434450"))
    )
    (comp (ref "LEDG112")
      (value "SZYY0402Y_C434450")
      (fields (field (name "Manufacturer Part") "SZYY0402Y") (field (name "Manufacturer") "yongyu(永裕光电)"))
      (libsource (lib "") (part "SZYY0402Y_C434450"))
    )
    (comp (ref "LEDG113")
      (value "SZYY0402Y_C434450")
      (fields (field (name "Manufacturer Part") "SZYY0402Y") (field (name "Manufacturer") "yongyu(永裕光电)"))
      (libsource (lib "") (part "SZYY0402Y_C434450"))
    )
    (comp (ref "LEDG114")
      (value "SZYY0402Y_C434450")
      (fields (field (name "Manufacturer Part") "SZYY0402Y") (field (name "Manufacturer") "yongyu(永裕光电)"))
      (libsource (lib "") (part "SZYY0402Y_C434450"))
    )
    (comp (ref "LEDG115")
      (value "SZYY0402Y_C434450")
      (fields (field (name "Manufacturer Part") "SZYY0402Y") (field (name "Manufacturer") "yongyu(永裕光电)"))
      (libsource (lib "") (part "SZYY0402Y_C434450"))
    )
    (comp (ref "LEDG116")
      (value "SZYY0402Y_C434450")
      (fields (field (name "Manufacturer Part") "SZYY0402Y") (field (name "Manufacturer") "yongyu(永裕光电)"))
      (libsource (lib "") (part "SZYY0402Y_C434450"))
    )
    (comp (ref "LEDG117")
      (value "SZYY0402Y_C434450")
      (fields (field (name "Manufacturer Part") "SZYY0402Y") (field (name "Manufacturer") "yongyu(永裕光电)"))
      (libsource (lib "") (part "SZYY0402Y_C434450"))
    )
    (comp (ref "LEDG118")
      (value "SZYY0402Y_C434450")
      (fields (field (name "Manufacturer Part") "SZYY0402Y") (field (name "Manufacturer") "yongyu(永裕光电)"))
      (libsource (lib "") (part "SZYY0402Y_C434450"))
    )
    (comp (ref "LEDG119")
      (value "SZYY0402Y_C434450")
      (fields (field (name "Manufacturer Part") "SZYY0402Y") (field (name "Manufacturer") "yongyu(永裕光电)"))
      (libsource (lib "") (part "SZYY0402Y_C434450"))
    )
    (comp (ref "LEDG120")
      (value "SZYY0402Y_C434450")
      (fields (field (name "Manufacturer Part") "SZYY0402Y") (field (name "Manufacturer") "yongyu(永裕光电)"))
      (libsource (lib "") (part "SZYY0402Y_C434450"))
    )
    (comp (ref "LEDG121")
      (value "SZYY0402Y_C434450")
      (fields (field (name "Manufacturer Part") "SZYY0402Y") (field (name "Manufacturer") "yongyu(永裕光电)"))
      (libsource (lib "") (part "SZYY0402Y_C434450"))
    )
    (comp (ref "LEDG122")
      (value "SZYY0402Y_C434450")
      (fields (field (name "Manufacturer Part") "SZYY0402Y") (field (name "Manufacturer") "yongyu(永裕光电)"))
      (libsource (lib "") (part "SZYY0402Y_C434450"))
    )
    (comp (ref "LEDG123")
      (value "SZYY0402Y_C434450")
      (fields (field (name "Manufacturer Part") "SZYY0402Y") (field (name "Manufacturer") "yongyu(永裕光电)"))
      (libsource (lib "") (part "SZYY0402Y_C434450"))
    )
    (comp (ref "LEDG124")
      (value "SZYY0402Y_C434450")
      (fields (field (name "Manufacturer Part") "SZYY0402Y") (field (name "Manufacturer") "yongyu(永裕光电)"))
      (libsource (lib "") (part "SZYY0402Y_C434450"))
    )
    (comp (ref "LEDG125")
      (value "SZYY0402Y_C434450")
      (fields (field (name "Manufacturer Part") "SZYY0402Y") (field (name "Manufacturer") "yongyu(永裕光电)"))
      (libsource (lib "") (part "SZYY0402Y_C434450"))
    )
    (comp (ref "LEDG126")
      (value "SZYY0402Y_C434450")
      (fields (field (name "Manufacturer Part") "SZYY0402Y") (field (name "Manufacturer") "yongyu(永裕光电)"))
      (libsource (lib "") (part "SZYY0402Y_C434450"))
    )
    (comp (ref "LEDG127")
      (value "SZYY0402Y_C434450")
      (fields (field (name "Manufacturer Part") "SZYY0402Y") (field (name "Manufacturer") "yongyu(永裕光电)"))
      (libsource (lib "") (part "SZYY0402Y_C434450"))
    )
    (comp (ref "LEDG128")
      (value "SZYY0402Y_C434450")
      (fields (field (name "Manufacturer Part") "SZYY0402Y") (field (name "Manufacturer") "yongyu(永裕光电)"))
      (libsource (lib "") (part "SZYY0402Y_C434450"))
    )
    (comp (ref "LEDG129")
      (value "SZYY0402Y_C434450")
      (fields (field (name "Manufacturer Part") "SZYY0402Y") (field (name "Manufacturer") "yongyu(永裕光电)"))
      (libsource (lib "") (part "SZYY0402Y_C434450"))
    )
    (comp (ref "LEDG130")
      (value "SZYY0402Y_C434450")
      (fields (field (name "Manufacturer Part") "SZYY0402Y") (field (name "Manufacturer") "yongyu(永裕光电)"))
      (libsource (lib "") (part "SZYY0402Y_C434450"))
    )
    (comp (ref "LEDG131")
      (value "SZYY0402Y_C434450")
      (fields (field (name "Manufacturer Part") "SZYY0402Y") (field (name "Manufacturer") "yongyu(永裕光电)"))
      (libsource (lib "") (part "SZYY0402Y_C434450"))
    )
    (comp (ref "LEDG132")
      (value "SZYY0402Y_C434450")
      (fields (field (name "Manufacturer Part") "SZYY0402Y") (field (name "Manufacturer") "yongyu(永裕光电)"))
      (libsource (lib "") (part "SZYY0402Y_C434450"))
    )
    (comp (ref "Q1")
      (value "NCE3401")
      (fields (field (name "Manufacturer") "NCE(无锡新洁能)"))
      (libsource (lib "") (part "NCE3401"))
    )
    (comp (ref "Q2")
      (value "2N7002")
      (fields (field (name "Manufacturer") "CJ(江苏长电/长晶)"))
      (libsource (lib "") (part "2N7002"))
    )
    (comp (ref "R1")
      (value "5.1kΩ")
      (fields
        (field (name "Manufacturer Part") "0603WAF5101T5E")
        (field (name "Manufacturer") "UNI-ROYAL(厚声)")
      )
      (libsource (lib "") (part "0603WAF5101T5E"))
    )
    (comp (ref "R2")
      (value "5.1kΩ")
      (fields
        (field (name "Manufacturer Part") "0603WAF5101T5E")
        (field (name "Manufacturer") "UNI-ROYAL(厚声)")
      )
      (libsource (lib "") (part "0603WAF5101T5E"))
    )
    (comp (ref "R3")
      (value "22Ω")
      (fields
        (field (name "Manufacturer Part") "0603WAF220JT5E")
        (field (name "Manufacturer") "UNI-ROYAL(厚声)")
      )
      (libsource (lib "") (part "0603WAF220JT5E"))
    )
    (comp (ref "R4")
      (value "22Ω")
      (fields
        (field (name "Manufacturer Part") "0603WAF220JT5E")
        (field (name "Manufacturer") "UNI-ROYAL(厚声)")
      )
      (libsource (lib "") (part "0603WAF220JT5E"))
    )
    (comp (ref "R5")
      (value "330Ω")
      (fields
        (field (name "Manufacturer Part") "0603WAF3300T5E")
        (field (name "Manufacturer") "UNI-ROYAL(厚声)")
      )
      (libsource (lib "") (part "0603WAF3300T5E"))
    )
    (comp (ref "R6")
      (value "10kΩ")
      (fields
        (field (name "Manufacturer Part") "0603WAF1002T5E")
        (field (name "Manufacturer") "UNI-ROYAL(厚声)")
      )
      (libsource (lib "") (part "0603WAF1002T5E"))
    )
    (comp (ref "R7")
      (value "10kΩ")
      (fields
        (field (name "Manufacturer Part") "0603WAF1002T5E")
        (field (name "Manufacturer") "UNI-ROYAL(厚声)")
      )
      (libsource (lib "") (part "0603WAF1002T5E"))
    )
    (comp (ref "R8")
      (value "100kΩ")
      (fields
        (field (name "Manufacturer Part") "0603WAF1003T5E")
        (field (name "Manufacturer") "UNI-ROYAL(厚声)")
      )
      (libsource (lib "") (part "0603WAF1003T5E"))
    )
    (comp (ref "R9")
      (value "10MΩ")
      (fields (field (name "Manufacturer Part") "RC0603FR-0710ML") (field (name "Manufacturer") "YAGEO(国巨)"))
      (libsource (lib "") (part "RC0603FR-0710ML"))
    )
    (comp (ref "R10")
      (value "1MΩ")
      (fields
        (field (name "Manufacturer Part") "0603WAF1004T5E")
        (field (name "Manufacturer") "UNI-ROYAL(厚声)")
      )
      (libsource (lib "") (part "0603WAF1004T5E"))
    )
    (comp (ref "R11")
      (value "2.2MΩ")
      (fields
        (field (name "Manufacturer Part") "0603WAF2204T5E")
        (field (name "Manufacturer") "UNI-ROYAL(厚声)")
      )
      (libsource (lib "") (part "0603WAF2204T5E"))
    )
    (comp (ref "R12")
      (value "4.7MΩ")
      (fields
        (field (name "Manufacturer Part") "0603WAF4704T5E")
        (field (name "Manufacturer") "UNI-ROYAL(厚声)")
      )
      (libsource (lib "") (part "0603WAF4704T5E"))
    )
    (comp (ref "R13")
      (value "470kΩ")
      (fields
        (field (name "Manufacturer Part") "0603WAF4703T5E")
        (field (name "Manufacturer") "UNI-ROYAL(厚声)")
      )
      (libsource (lib "") (part "0603WAF4703T5E"))
    )
    (comp (ref "R14")
      (value "10kΩ")
      (fields
        (field (name "Manufacturer Part") "0603WAF1002T5E")
        (field (name "Manufacturer") "UNI-ROYAL(厚声)")
      )
      (libsource (lib "") (part "0603WAF1002T5E"))
    )
    (comp (ref "R15")
      (value "10kΩ")
      (fields
        (field (name "Manufacturer Part") "0603WAF1002T5E")
        (field (name "Manufacturer") "UNI-ROYAL(厚声)")
      )
      (libsource (lib "") (part "0603WAF1002T5E"))
    )
    (comp (ref "R16")
      (value "47kΩ")
      (fields
        (field (name "Manufacturer Part") "0603WAF4702T5E")
        (field (name "Manufacturer") "UNI-ROYAL(厚声)")
      )
      (libsource (lib "") (part "0603WAF4702T5E"))
    )
    (comp (ref "R17")
      (value "47kΩ")
      (fields
        (field (name "Manufacturer Part") "0603WAF4702T5E")
        (field (name "Manufacturer") "UNI-ROYAL(厚声)")
      )
      (libsource (lib "") (part "0603WAF4702T5E"))
    )
    (comp (ref "R18")
      (value "10kΩ")
      (fields
        (field (name "Manufacturer Part") "0603WAF1002T5E")
        (field (name "Manufacturer") "UNI-ROYAL(厚声)")
      )
      (libsource (lib "") (part "0603WAF1002T5E"))
    )
    (comp (ref "R19")
      (value "10kΩ")
      (fields
        (field (name "Manufacturer Part") "0603WAF1002T5E")
        (field (name "Manufacturer") "UNI-ROYAL(厚声)")
      )
      (libsource (lib "") (part "0603WAF1002T5E"))
    )
    (comp (ref "R22")
      (value "0Ω")
      (fields
        (field (name "Manufacturer Part") "0603WAF0000T5E")
        (field (name "Manufacturer") "UNI-ROYAL(厚声)")
      )
      (libsource (lib "") (part "0603WAF0000T5E"))
    )
    (comp (ref "R23")
      (value "330Ω")
      (fields
        (field (name "Manufacturer Part") "0603WAF3300T5E")
        (field (name "Manufacturer") "UNI-ROYAL(厚声)")
      )
      (libsource (lib "") (part "0603WAF3300T5E_1"))
    )
    (comp (ref "R24")
      (value "47kΩ")
      (fields
        (field (name "Manufacturer Part") "0603WAF4702T5E")
        (field (name "Manufacturer") "UNI-ROYAL(厚声)")
      )
      (libsource (lib "") (part "0603WAF4702T5E"))
    )
    (comp (ref "R25")
      (value "330Ω")
      (fields
        (field (name "Manufacturer Part") "0603WAF3300T5E")
        (field (name "Manufacturer") "UNI-ROYAL(厚声)")
      )
      (libsource (lib "") (part "0603WAF3300T5E_1"))
    )
    (comp (ref "R26")
      (value "330Ω")
      (fields
        (field (name "Manufacturer Part") "0603WAF3300T5E")
        (field (name "Manufacturer") "UNI-ROYAL(厚声)")
      )
      (libsource (lib "") (part "0603WAF3300T5E"))
    )
    (comp (ref "R27")
      (value "470kΩ")
      (fields
        (field (name "Manufacturer Part") "0603WAF4703T5E")
        (field (name "Manufacturer") "UNI-ROYAL(厚声)")
      )
      (libsource (lib "") (part "0603WAF4703T5E"))
    )
    (comp (ref "R28")
      (value "1.2MΩ")
      (fields
        (field (name "Manufacturer Part") "0603WAF1204T5E")
        (field (name "Manufacturer") "UNI-ROYAL(厚声)")
      )
      (libsource (lib "") (part "0603WAF1204T5E_C13315"))
    )
    (comp (ref "SW1")
      (value "POWER")
      (fields (field (name "Manufacturer Part") "K2-1806SA-C4DW-04") (field (name "Manufacturer") "韩国韩荣"))
      (libsource (lib "") (part "K2-1806SA-C4DW-04"))
    )
    (comp (ref "SW2")
      (value "RESET")
      (fields (field (name "Manufacturer Part") "K2-1806SA-C4DW-04") (field (name "Manufacturer") "韩国韩荣"))
      (libsource (lib "") (part "K2-1806SA-C4DW-04"))
    )
    (comp (ref "SW3")
      (value "BOOT")
      (fields (field (name "Manufacturer Part") "K2-1806SA-C4DW-04") (field (name "Manufacturer") "韩国韩荣"))
      (libsource (lib "") (part "K2-1806SA-C4DW-04"))
    )
    (comp (ref "TP1")
      (value "PWR")
      (fields (field (name "Manufacturer Part") "TESTPAD"))
      (libsource (lib "") (part "TEST_PAD"))
    )
    (comp (ref "TP2")
      (value "TXD")
      (fields (field (name "Manufacturer Part") "TESTPAD"))
      (libsource (lib "") (part "TEST_PAD"))
    )
    (comp (ref "TP3")
      (value "EN")
      (fields (field (name "Manufacturer Part") "TESTPAD"))
      (libsource (lib "") (part "TEST_PAD"))
    )
    (comp (ref "TP4")
      (value "CHG")
      (fields (field (name "Manufacturer Part") "TESTPAD"))
      (libsource (lib "") (part "TEST_PAD_1"))
    )
    (comp (ref "TP5")
      (value "INT2")
      (fields (field (name "Manufacturer Part") "TESTPAD"))
      (libsource (lib "") (part "TEST_PAD_1"))
    )
    (comp (ref "TP6")
      (value "SCL")
      (fields (field (name "Manufacturer Part") "TESTPAD"))
      (libsource (lib "") (part "TEST_PAD_1"))
    )
    (comp (ref "TP7")
      (value "SDA")
      (fields (field (name "Manufacturer Part") "TESTPAD"))
      (libsource (lib "") (part "TEST_PAD_1"))
    )
    (comp (ref "TP8")
      (value "VBAT")
      (fields (field (name "Manufacturer Part") "TESTPAD"))
      (libsource (lib "") (part "TEST_PAD"))
    )
    (comp (ref "TP9")
      (value "WAKE")
      (fields (field (name "Manufacturer Part") "TESTPAD"))
      (libsource (lib "") (part "TEST_PAD"))
    )
    (comp (ref "TP10")
      (value "GND")
      (fields (field (name "Manufacturer Part") "TESTPAD"))
      (libsource (lib "") (part "TEST_PAD"))
    )
    (comp (ref "U1")
      (value "ESP32-C6_C5364646")
      (fields (field (name "Manufacturer Part") "ESP32-C6") (field (name "Manufacturer") "ESPRESSIF(乐鑫)"))
      (libsource (lib "") (part "ESP32-C6_C5364646"))
    )
    (comp (ref "U2")
      (value "W25Q32JVUUIQ")
      (fields (field (name "Manufacturer") "Winbond(华邦)"))
      (libsource (lib "") (part "W25Q32JVUUIQ"))
    )
    (comp (ref "U4")
      (value "MCP73831T-2ACI/OT")
      (fields (field (name "Manufacturer") "MICROCHIP(美国微芯)"))
      (libsource (lib "") (part "MCP73831T-2ACI/OT"))
    )
    (comp (ref "U5")
      (value "ANT3216LL00R2400A")
      (fields (field (name "Manufacturer") "YAGEO(国巨)"))
      (libsource (lib "") (part "ANT3216LL00R2400A"))
    )
    (comp (ref "U6")
      (value "XC6210B332MR")
      (fields (field (name "Manufacturer Part") "XC6210B332MR-G") (field (name "Manufacturer") "TOREX(特瑞仕)"))
      (libsource (lib "") (part "XC6210B332MR"))
    )
    (comp (ref "U7")
      (value "BAS100CS-AU_R1_000A1")
      (fields (field (name "Manufacturer") "PANJIT(强茂)"))
      (libsource (lib "") (part "BAS100CS-AU_R1_000A1"))
    )
    (comp (ref "U8")
      (value "TS5A23157DGSR")
      (fields (field (name "Manufacturer") "TI(德州仪器)"))
      (libsource (lib "") (part "TS5A23157DGSR"))
    )
    (comp (ref "U14")
      (value "LSM6DS3TR-C")
      (fields (field (name "Manufacturer") "ST(意法半导体)"))
      (libsource (lib "") (part "LSM6DS3TR-C"))
    )
    (comp (ref "U15")
      (value "RV-3028-C7 32.768KHZ 1PPM TA QC")
      (fields
        (field (name "Manufacturer Part") "RV-3028-C7-32.768kHz-1ppm-TA-QC")
        (field (name "Manufacturer") "Micro Crystal(瑞士微晶)")
      )
      (libsource (lib "") (part "RV-3028-C7 32.768KHZ 1PPM TA QC"))
    )
    (comp (ref "USB1")
      (value "TYPE-C 16P QTWT")
      (fields (field (name "Manufacturer") "SHOU HAN(首韩)"))
      (libsource (lib "") (part "TYPE-C 16P QTWT"))
    )
    (comp (ref "X1")
      (value "40MHz")
      (fields
        (field (name "Manufacturer Part") "CJ17-400001010B20")
        (field (name "Manufacturer") "CJ(江苏长电/长晶)")
      )
      (libsource (lib "") (part "CJ17-400001010B20"))
    )
  )
  (nets
    (net (code "1") (name "+3V3") (class "Default")
      (node (ref "C13") (pin "2") (pinfunction "2_2") (pintype "unspecified"))
      (node (ref "C15") (pin "2") (pinfunction "2_2") (pintype "unspecified"))
      (node (ref "C4") (pin "2") (pinfunction "2_2") (pintype "unspecified"))
      (node (ref "C5") (pin "2") (pinfunction "2_2") (pintype "unspecified"))
      (node (ref "R14") (pin "2") (pinfunction "2_2") (pintype "input"))
      (node (ref "R16") (pin "2") (pinfunction "2_2") (pintype "input"))
      (node (ref "R17") (pin "2") (pinfunction "2_2") (pintype "input"))
      (node (ref "R18") (pin "2") (pinfunction "2_2") (pintype "input"))
      (node (ref "R19") (pin "2") (pinfunction "2_2") (pintype "input"))
      (node (ref "R24") (pin "2") (pinfunction "2_2") (pintype "input"))
      (node (ref "R6") (pin "2") (pinfunction "2_2") (pintype "input"))
      (node (ref "U1") (pin "2") (pinfunction "VDDA3P3_2") (pintype "unspecified"))
      (node (ref "U1") (pin "28") (pinfunction "VDDPST2_28") (pintype "unspecified"))
      (node (ref "U1") (pin "3") (pinfunction "VDDA3P3_3") (pintype "unspecified"))
      (node (ref "U1") (pin "37") (pinfunction "VDDA1_37") (pintype "unspecified"))
      (node (ref "U1") (pin "40") (pinfunction "VDDA2_40") (pintype "unspecified"))
      (node (ref "U1") (pin "5") (pinfunction "VDDPST1_5") (pintype "unspecified"))
      (node (ref "U14") (pin "5") (pinfunction "VDDIO_5") (pintype "unspecified"))
      (node (ref "U14") (pin "8") (pinfunction "VDD_8") (pintype "unspecified"))
      (node (ref "U15") (pin "7") (pinfunction "VDD_7") (pintype "unspecified"))
      (node (ref "U6") (pin "5") (pinfunction "OUT_5") (pintype "unspecified"))
      (node (ref "U8") (pin "8") (pinfunction "V+_8") (pintype "unspecified"))
    )
    (net (code "2") (name "ANT") (class "Default")
      (node (ref "C2") (pin "2") (pinfunction "2_2") (pintype "input"))
      (node (ref "L1") (pin "2") (pinfunction "2_2") (pintype "unspecified"))
      (node (ref "U1") (pin "1") (pinfunction "ANT_1") (pintype "unspecified"))
    )
    (net (code "3") (name "BOOT") (class "Default")
      (node (ref "D6") (pin "1") (pinfunction "K_1") (pintype "unspecified"))
      (node (ref "R5") (pin "2") (pinfunction "2_2") (pintype "input"))
      (node (ref "U1") (pin "15") (pinfunction "GPIO9_15") (pintype "unspecified"))
    )
    (net (code "4") (name "ESP32_EN") (class "Default")
      (node (ref "C6") (pin "2") (pinfunction "2_2") (pintype "unspecified"))
      (node (ref "R6") (pin "1") (pinfunction "1_1") (pintype "input"))
      (node (ref "SW2") (pin "2") (pinfunction "2_2") (pintype "unspecified"))
      (node (ref "TP3") (pin "1") (pinfunction "1_1") (pintype "unspecified"))
      (node (ref "U1") (pin "4") (pinfunction "CHIP_PU_4") (pintype "unspecified"))
    )
    (net (code "5") (name "GND") (class "Default")
      (node (ref "C1") (pin "1") (pinfunction "1_1") (pintype "input"))
      (node (ref "C11") (pin "1") (pinfunction "1_1") (pintype "unspecified"))
      (node (ref "C12") (pin "1") (pinfunction "1_1") (pintype "unspecified"))
      (node (ref "C13") (pin "1") (pinfunction "1_1") (pintype "unspecified"))
      (node (ref "C14") (pin "1") (pinfunction "1_1") (pintype "unspecified"))
      (node (ref "C15") (pin "1") (pinfunction "1_1") (pintype "unspecified"))
      (node (ref "C16") (pin "1") (pinfunction "1_1") (pintype "unspecified"))
      (node (ref "C17") (pin "1") (pinfunction "1_1") (pintype "input"))
      (node (ref "C2") (pin "1") (pinfunction "1_1") (pintype "input"))
      (node (ref "C3") (pin "1") (pinfunction "1_1") (pintype "unspecified"))
      (node (ref "C4") (pin "1") (pinfunction "1_1") (pintype "unspecified"))
      (node (ref "C5") (pin "1") (pinfunction "1_1") (pintype "unspecified"))
      (node (ref "C6") (pin "1") (pinfunction "1_1") (pintype "unspecified"))
      (node (ref "C7") (pin "1") (pinfunction "1_1") (pintype "input"))
      (node (ref "C8") (pin "1") (pinfunction "1_1") (pintype "input"))
      (node (ref "CN1") (pin "2") (pinfunction "2_2") (pintype "unspecified"))
      (node (ref "CN1") (pin "3") (pinfunction "3_3") (pintype "unspecified"))
      (node (ref "CN1") (pin "4") (pinfunction "4_4") (pintype "unspecified"))
      (node (ref "Q2") (pin "2") (pinfunction "S_2") (pintype "unspecified"))
      (node (ref "R1") (pin "1") (pinfunction "1_1") (pintype "input"))
      (node (ref "R11") (pin "1") (pinfunction "1_1") (pintype "input"))
      (node (ref "R13") (pin "1") (pinfunction "1_1") (pintype "input"))
      (node (ref "R15") (pin "1") (pinfunction "1_1") (pintype "input"))
      (node (ref "R2") (pin "1") (pinfunction "1_1") (pintype "input"))
      (node (ref "R27") (pin "1") (pinfunction "1_1") (pintype "input"))
      (node (ref "R28") (pin "1") (pinfunction "1_1") (pintype "input"))
      (node (ref "R7") (pin "1") (pinfunction "1_1") (pintype "input"))
      (node (ref "R8") (pin "1") (pinfunction "1_1") (pintype "input"))
      (node (ref "R9") (pin "1") (pinfunction "1_1") (pintype "input"))
      (node (ref "SW2") (pin "1") (pinfunction "1_1") (pintype "unspecified"))
      (node (ref "SW2") (pin "3") (pinfunction "3_3") (pintype "unspecified"))
      (node (ref "SW2") (pin "4") (pinfunction "4_4") (pintype "unspecified"))
      (node (ref "SW3") (pin "1") (pinfunction "1_1") (pintype "unspecified"))
      (node (ref "SW3") (pin "3") (pinfunction "3_3") (pintype "unspecified"))
      (node (ref "SW3") (pin "4") (pinfunction "4_4") (pintype "unspecified"))
      (node (ref "TP10") (pin "1") (pinfunction "1_1") (pintype "unspecified"))
      (node (ref "U1") (pin "41") (pinfunction "EP_41") (pintype "unspecified"))
      (node (ref "U14") (pin "6") (pinfunction "GND_6") (pintype "unspecified"))
      (node (ref "U14") (pin "7") (pinfunction "GND_7") (pintype "unspecified"))
      (node (ref "U15") (pin "5") (pinfunction "VSS_5") (pintype "unspecified"))
      (node (ref "U2") (pin "10") (pinfunction "EP2_10") (pintype "unspecified"))
      (node (ref "U2") (pin "4") (pinfunction "GND_4") (pintype "unspecified"))
      (node (ref "U2") (pin "9") (pinfunction "EP1_9") (pintype "unspecified"))
      (node (ref "U4") (pin "2") (pinfunction "VSS_2") (pintype "unspecified"))
      (node (ref "U6") (pin "2") (pinfunction "GND_2") (pintype "unspecified"))
      (node (ref "U8") (pin "3") (pinfunction "GND_3") (pintype "unspecified"))
      (node (ref "USB1") (pin "0") (pinfunction "EH_0") (pintype "unspecified"))
      (node (ref "USB1") (pin "A1") (pinfunction "GND_A1") (pintype "unspecified"))
      (node (ref "USB1") (pin "A12") (pinfunction "GND_A12") (pintype "unspecified"))
      (node (ref "X1") (pin "2") (pinfunction "GND_2") (pintype "input"))
      (node (ref "X1") (pin "4") (pinfunction "GND_4") (pintype "input"))
    )
    (net (code "6") (name "GPIO0") (class "Default")
      (node (ref "R22") (pin "1") (pinfunction "1_1") (pintype "input"))
      (node (ref "U1") (pin "6") (pinfunction "XTAL_32K_P_6") (pintype "unspecified"))
    )
    (net (code "7") (name "I2C1_SCL") (class "Default")
      (node (ref "R17") (pin "1") (pinfunction "1_1") (pintype "input"))
      (node (ref "TP6") (pin "1") (pinfunction "1_1") (pintype "unspecified"))
      (node (ref "U14") (pin "13") (pinfunction "SCL_13") (pintype "unspecified"))
      (node (ref "U15") (pin "3") (pinfunction "SCL_3") (pintype "unspecified"))
      (node (ref "U8") (pin "2") (pinfunction "NO_1_2") (pintype "unspecified"))
    )
    (net (code "8") (name "I2C1_SCL_STRAP") (class "Default")
      (node (ref "R19") (pin "1") (pinfunction "1_1") (pintype "input"))
      (node (ref "U1") (pin "14") (pinfunction "GPIO8_14") (pintype "unspecified"))
      (node (ref "U8") (pin "10") (pinfunction "COM_1_10") (pintype "unspecified"))
    )
    (net (code "9") (name "I2C1_SDA") (class "Default")
      (node (ref "R16") (pin "1") (pinfunction "1_1") (pintype "input"))
      (node (ref "TP7") (pin "1") (pinfunction "1_1") (pintype "unspecified"))
      (node (ref "U1") (pin "12") (pinfunction "MTCK_12") (pintype "unspecified"))
      (node (ref "U14") (pin "14") (pinfunction "SDA_14") (pintype "unspecified"))
      (node (ref "U15") (pin "4") (pinfunction "SDA_4") (pintype "unspecified"))
    )
    (net (code "10") (name "IMU_INT2#") (class "Default")
      (node (ref "R25") (pin "2") (pinfunction "2_2") (pintype "input"))
      (node (ref "TP5") (pin "1") (pinfunction "1_1") (pintype "unspecified"))
      (node (ref "U14") (pin "9") (pinfunction "INT2_9") (pintype "unspecified"))
    )
    (net (code "11") (name "Net-(C1-Pad2)") (class "Default")
      (node (ref "C1") (pin "2") (pinfunction "2_2") (pintype "input"))
      (node (ref "L1") (pin "1") (pinfunction "1_1") (pintype "unspecified"))
      (node (ref "U5") (pin "1") (pinfunction "1_1") (pintype "unspecified"))
    )
    (net (code "12") (name "Net-(D1-K)") (class "Default")
      (node (ref "C14") (pin "2") (pinfunction "2_2") (pintype "unspecified"))
      (node (ref "D1") (pin "1") (pinfunction "K_1") (pintype "unspecified"))
      (node (ref "D2") (pin "1") (pinfunction "K_1") (pintype "unspecified"))
      (node (ref "D4") (pin "1") (pinfunction "K_1") (pintype "unspecified"))
      (node (ref "R9") (pin "2") (pinfunction "2_2") (pintype "input"))
      (node (ref "U6") (pin "3") (pinfunction "CE_3") (pintype "unspecified"))
    )
    (net (code "13") (name "Net-(D3-K)") (class "Default")
      (node (ref "D3") (pin "1") (pinfunction "K_1") (pintype "unspecified"))
      (node (ref "Q1") (pin "1") (pinfunction "G_1") (pintype "unspecified"))
      (node (ref "R8") (pin "2") (pinfunction "2_2") (pintype "input"))
    )
    (net (code "14") (name "Net-(D5-K)") (class "Default")
      (node (ref "D5") (pin "1") (pinfunction "K_1") (pintype "unspecified"))
      (node (ref "R10") (pin "1") (pinfunction "1_1") (pintype "input"))
    )
    (net (code "15") (name "Net-(Q1-S)") (class "Default")
      (node (ref "C12") (pin "2") (pinfunction "2_2") (pintype "unspecified"))
      (node (ref "Q1") (pin "2") (pinfunction "S_2") (pintype "unspecified"))
      (node (ref "U6") (pin "1") (pinfunction "IN_1") (pintype "unspecified"))
      (node (ref "U7") (pin "1") (pinfunction "C_1") (pintype "unspecified"))
    )
    (net (code "16") (name "Net-(Q2-D)") (class "Default")
      (node (ref "Q2") (pin "3") (pinfunction "D_3") (pintype "unspecified"))
      (node (ref "R26") (pin "1") (pinfunction "1_1") (pintype "input"))
    )
    (net (code "17") (name "Net-(R5-Pad1)") (class "Default")
      (node (ref "R5") (pin "1") (pinfunction "1_1") (pintype "input"))
      (node (ref "SW3") (pin "2") (pinfunction "2_2") (pintype "unspecified"))
    )
    (net (code "18") (name "Net-(U1-GPIO12)") (class "Default")
      (node (ref "R3") (pin "1") (pinfunction "1_1") (pintype "input"))
      (node (ref "U1") (pin "18") (pinfunction "GPIO12_18") (pintype "unspecified"))
    )
    (net (code "19") (name "Net-(U1-GPIO13)") (class "Default")
      (node (ref "R4") (pin "1") (pinfunction "1_1") (pintype "input"))
      (node (ref "U1") (pin "19") (pinfunction "GPIO13_19") (pintype "unspecified"))
    )
    (net (code "20") (name "Net-(U4-PROG)") (class "Default")
      (node (ref "R7") (pin "2") (pinfunction "2_2") (pintype "input"))
      (node (ref "U4") (pin "5") (pinfunction "PROG_5") (pintype "unspecified"))
    )
    (net (code "21") (name "Net-(U4-STAT)") (class "Default")
      (node (ref "TP4") (pin "1") (pinfunction "1_1") (pintype "unspecified"))
      (node (ref "U4") (pin "1") (pinfunction "STAT_1") (pintype "unspecified"))
    )
    (net (code "22") (name "Net-(U14-CS)") (class "Default")
      (node (ref "R14") (pin "1") (pinfunction "1_1") (pintype "input"))
      (node (ref "U14") (pin "12") (pinfunction "CS_12") (pintype "unspecified"))
    )
    (net (code "23") (name "Net-(U14-SDO{slash}SA0)") (class "Default")
      (node (ref "R15") (pin "2") (pinfunction "2_2") (pintype "input"))
      (node (ref "U14") (pin "1") (pinfunction "SDO/SA0_1") (pintype "unspecified"))
    )
    (net (code "24") (name "Net-(U15-EVI)") (class "Default")
      (node (ref "R18") (pin "1") (pinfunction "1_1") (pintype "input"))
      (node (ref "U15") (pin "8") (pinfunction "EVI_8") (pintype "unspecified"))
    )
    (net (code "25") (name "Net-(USB1-CC1)") (class "Default")
      (node (ref "R1") (pin "2") (pinfunction "2_2") (pintype "input"))
      (node (ref "USB1") (pin "A5") (pinfunction "CC1_A5") (pintype "unspecified"))
    )
    (net (code "26") (name "Net-(USB1-CC2)") (class "Default")
      (node (ref "R2") (pin "2") (pinfunction "2_2") (pintype "input"))
      (node (ref "USB1") (pin "B5") (pinfunction "CC2_B5") (pintype "unspecified"))
    )
    (net (code "27") (name "P1") (class "Default")
      (node (ref "LEDG1") (pin "1") (pinfunction "A_1") (pintype "unspecified"))
      (node (ref "LEDG10") (pin "1") (pinfunction "A_1") (pintype "unspecified"))
      (node (ref "LEDG100") (pin "2") (pinfunction "K_2") (pintype "unspecified"))
      (node (ref "LEDG11") (pin "1") (pinfunction "A_1") (pintype "unspecified"))
      (node (ref "LEDG111") (pin "2") (pinfunction "K_2") (pintype "unspecified"))
      (node (ref "LEDG12") (pin "2") (pinfunction "K_2") (pintype "unspecified"))
      (node (ref "LEDG122") (pin "2") (pinfunction "K_2") (pintype "unspecified"))
      (node (ref "LEDG2") (pin "1") (pinfunction "A_1") (pintype "unspecified"))
      (node (ref "LEDG23") (pin "2") (pinfunction "K_2") (pintype "unspecified"))
      (node (ref "LEDG3") (pin "1") (pinfunction "A_1") (pintype "unspecified"))
      (node (ref "LEDG34") (pin "2") (pinfunction "K_2") (pintype "unspecified"))
      (node (ref "LEDG4") (pin "1") (pinfunction "A_1") (pintype "unspecified"))
      (node (ref "LEDG45") (pin "2") (pinfunction "K_2") (pintype "unspecified"))
      (node (ref "LEDG5") (pin "1") (pinfunction "A_1") (pintype "unspecified"))
      (node (ref "LEDG56") (pin "2") (pinfunction "K_2") (pintype "unspecified"))
      (node (ref "LEDG6") (pin "1") (pinfunction "A_1") (pintype "unspecified"))
      (node (ref "LEDG67") (pin "2") (pinfunction "K_2") (pintype "unspecified"))
      (node (ref "LEDG7") (pin "1") (pinfunction "A_1") (pintype "unspecified"))
      (node (ref "LEDG78") (pin "2") (pinfunction "K_2") (pintype "unspecified"))
      (node (ref "LEDG8") (pin "1") (pinfunction "A_1") (pintype "unspecified"))
      (node (ref "LEDG89") (pin "2") (pinfunction "K_2") (pintype "unspecified"))
      (node (ref "LEDG9") (pin "1") (pinfunction "A_1") (pintype "unspecified"))
      (node (ref "U1") (pin "16") (pinfunction "GPIO10_16") (pintype "unspecified"))
    )
    (net (code "28") (name "P2") (class "Default")
      (node (ref "LEDG1") (pin "2") (pinfunction "K_2") (pintype "unspecified"))
      (node (ref "LEDG101") (pin "2") (pinfunction "K_2") (pintype "unspecified"))
      (node (ref "LEDG112") (pin "2") (pinfunction "K_2") (pintype "unspecified"))
      (node (ref "LEDG12") (pin "1") (pinfunction "A_1") (pintype "unspecified"))
      (node (ref "LEDG123") (pin "2") (pinfunction "K_2") (pintype "unspecified"))
      (node (ref "LEDG13") (pin "1") (pinfunction "A_1") (pintype "unspecified"))
      (node (ref "LEDG14") (pin "1") (pinfunction "A_1") (pintype "unspecified"))
      (node (ref "LEDG15") (pin "1") (pinfunction "A_1") (pintype "unspecified"))
      (node (ref "LEDG16") (pin "1") (pinfunction "A_1") (pintype "unspecified"))
      (node (ref "LEDG17") (pin "1") (pinfunction "A_1") (pintype "unspecified"))
      (node (ref "LEDG18") (pin "1") (pinfunction "A_1") (pintype "unspecified"))
      (node (ref "LEDG19") (pin "1") (pinfunction "A_1") (pintype "unspecified"))
      (node (ref "LEDG20") (pin "1") (pinfunction "A_1") (pintype "unspecified"))
      (node (ref "LEDG21") (pin "1") (pinfunction "A_1") (pintype "unspecified"))
      (node (ref "LEDG22") (pin "1") (pinfunction "A_1") (pintype "unspecified"))
      (node (ref "LEDG24") (pin "2") (pinfunction "K_2") (pintype "unspecified"))
      (node (ref "LEDG35") (pin "2") (pinfunction "K_2") (pintype "unspecified"))
      (node (ref "LEDG46") (pin "2") (pinfunction "K_2") (pintype "unspecified"))
      (node (ref "LEDG57") (pin "2") (pinfunction "K_2") (pintype "unspecified"))
      (node (ref "LEDG68") (pin "2") (pinfunction "K_2") (pintype "unspecified"))
      (node (ref "LEDG79") (pin "2") (pinfunction "K_2") (pintype "unspecified"))
      (node (ref "LEDG90") (pin "2") (pinfunction "K_2") (pintype "unspecified"))
      (node (ref "U1") (pin "17") (pinfunction "GPIO11_17") (pintype "unspecified"))
    )
    (net (code "29") (name "P3") (class "Default")
      (node (ref "LEDG102") (pin "2") (pinfunction "K_2") (pintype "unspecified"))
      (node (ref "LEDG113") (pin "2") (pinfunction "K_2") (pintype "unspecified"))
      (node (ref "LEDG124") (pin "2") (pinfunction "K_2") (pintype "unspecified"))
      (node (ref "LEDG13") (pin "2") (pinfunction "K_2") (pintype "unspecified"))
      (node (ref "LEDG2") (pin "2") (pinfunction "K_2") (pintype "unspecified"))
      (node (ref "LEDG23") (pin "1") (pinfunction "A_1") (pintype "unspecified"))
      (node (ref "LEDG24") (pin "1") (pinfunction "A_1") (pintype "unspecified"))
      (node (ref "LEDG25") (pin "1") (pinfunction "A_1") (pintype "unspecified"))
      (node (ref "LEDG26") (pin "1") (pinfunction "A_1") (pintype "unspecified"))
      (node (ref "LEDG27") (pin "1") (pinfunction "A_1") (pintype "unspecified"))
      (node (ref "LEDG28") (pin "1") (pinfunction "A_1") (pintype "unspecified"))
      (node (ref "LEDG29") (pin "1") (pinfunction "A_1") (pintype "unspecified"))
      (node (ref "LEDG30") (pin "1") (pinfunction "A_1") (pintype "unspecified"))
      (node (ref "LEDG31") (pin "1") (pinfunction "A_1") (pintype "unspecified"))
      (node (ref "LEDG32") (pin "1") (pinfunction "A_1") (pintype "unspecified"))
      (node (ref "LEDG33") (pin "1") (pinfunction "A_1") (pintype "unspecified"))
      (node (ref "LEDG36") (pin "2") (pinfunction "K_2") (pintype "unspecified"))
      (node (ref "LEDG47") (pin "2") (pinfunction "K_2") (pintype "unspecified"))
      (node (ref "LEDG58") (pin "2") (pinfunction "K_2") (pintype "unspecified"))
      (node (ref "LEDG69") (pin "2") (pinfunction "K_2") (pintype "unspecified"))
      (node (ref "LEDG80") (pin "2") (pinfunction "K_2") (pintype "unspecified"))
      (node (ref "LEDG91") (pin "2") (pinfunction "K_2") (pintype "unspecified"))
      (node (ref "U1") (pin "31") (pinfunction "SDIO_CMD_31") (pintype "unspecified"))
    )
    (net (code "30") (name "P4") (class "Default")
      (node (ref "LEDG103") (pin "2") (pinfunction "K_2") (pintype "unspecified"))
      (node (ref "LEDG114") (pin "2") (pinfunction "K_2") (pintype "unspecified"))
      (node (ref "LEDG125") (pin "2") (pinfunction "K_2") (pintype "unspecified"))
      (node (ref "LEDG14") (pin "2") (pinfunction "K_2") (pintype "unspecified"))
      (node (ref "LEDG25") (pin "2") (pinfunction "K_2") (pintype "unspecified"))
      (node (ref "LEDG3") (pin "2") (pinfunction "K_2") (pintype "unspecified"))
      (node (ref "LEDG34") (pin "1") (pinfunction "A_1") (pintype "unspecified"))
      (node (ref "LEDG35") (pin "1") (pinfunction "A_1") (pintype "unspecified"))
      (node (ref "LEDG36") (pin "1") (pinfunction "A_1") (pintype "unspecified"))
      (node (ref "LEDG37") (pin "1") (pinfunction "A_1") (pintype "unspecified"))
      (node (ref "LEDG38") (pin "1") (pinfunction "A_1") (pintype "unspecified"))
      (node (ref "LEDG39") (pin "1") (pinfunction "A_1") (pintype "unspecified"))
      (node (ref "LEDG40") (pin "1") (pinfunction "A_1") (pintype "unspecified"))
      (node (ref "LEDG41") (pin "1") (pinfunction "A_1") (pintype "unspecified"))
      (node (ref "LEDG42") (pin "1") (pinfunction "A_1") (pintype "unspecified"))
      (node (ref "LEDG43") (pin "1") (pinfunction "A_1") (pintype "unspecified"))
      (node (ref "LEDG44") (pin "1") (pinfunction "A_1") (pintype "unspecified"))
      (node (ref "LEDG48") (pin "2") (pinfunction "K_2") (pintype "unspecified"))
      (node (ref "LEDG59") (pin "2") (pinfunction "K_2") (pintype "unspecified"))
      (node (ref "LEDG70") (pin "2") (pinfunction "K_2") (pintype "unspecified"))
      (node (ref "LEDG81") (pin "2") (pinfunction "K_2") (pintype "unspecified"))
      (node (ref "LEDG92") (pin "2") (pinfunction "K_2") (pintype "unspecified"))
      (node (ref "U1") (pin "32") (pinfunction "SDIO_CLK_32") (pintype "unspecified"))
    )
    (net (code "31") (name "P5") (class "Default")
      (node (ref "LEDG104") (pin "2") (pinfunction "K_2") (pintype "unspecified"))
      (node (ref "LEDG115") (pin "2") (pinfunction "K_2") (pintype "unspecified"))
      (node (ref "LEDG126") (pin "2") (pinfunction "K_2") (pintype "unspecified"))
      (node (ref "LEDG15") (pin "2") (pinfunction "K_2") (pintype "unspecified"))
      (node (ref "LEDG26") (pin "2") (pinfunction "K_2") (pintype "unspecified"))
      (node (ref "LEDG37") (pin "2") (pinfunction "K_2") (pintype "unspecified"))
      (node (ref "LEDG4") (pin "2") (pinfunction "K_2") (pintype "unspecified"))
      (node (ref "LEDG45") (pin "1") (pinfunction "A_1") (pintype "unspecified"))
      (node (ref "LEDG46") (pin "1") (pinfunction "A_1") (pintype "unspecified"))
      (node (ref "LEDG47") (pin "1") (pinfunction "A_1") (pintype "unspecified"))
      (node (ref "LEDG48") (pin "1") (pinfunction "A_1") (pintype "unspecified"))
      (node (ref "LEDG49") (pin "1") (pinfunction "A_1") (pintype "unspecified"))
      (node (ref "LEDG50") (pin "1") (pinfunction "A_1") (pintype "unspecified"))
      (node (ref "LEDG51") (pin "1") (pinfunction "A_1") (pintype "unspecified"))
      (node (ref "LEDG52") (pin "1") (pinfunction "A_1") (pintype "unspecified"))
      (node (ref "LEDG53") (pin "1") (pinfunction "A_1") (pintype "unspecified"))
      (node (ref "LEDG54") (pin "1") (pinfunction "A_1") (pintype "unspecified"))
      (node (ref "LEDG55") (pin "1") (pinfunction "A_1") (pintype "unspecified"))
      (node (ref "LEDG60") (pin "2") (pinfunction "K_2") (pintype "unspecified"))
      (node (ref "LEDG71") (pin "2") (pinfunction "K_2") (pintype "unspecified"))
      (node (ref "LEDG82") (pin "2") (pinfunction "K_2") (pintype "unspecified"))
      (node (ref "LEDG93") (pin "2") (pinfunction "K_2") (pintype "unspecified"))
      (node (ref "U1") (pin "33") (pinfunction "SDIO_DATA0_33") (pintype "unspecified"))
    )
    (net (code "32") (name "P6") (class "Default")
      (node (ref "LEDG105") (pin "2") (pinfunction "K_2") (pintype "unspecified"))
      (node (ref "LEDG116") (pin "2") (pinfunction "K_2") (pintype "unspecified"))
      (node (ref "LEDG127") (pin "2") (pinfunction "K_2") (pintype "unspecified"))
      (node (ref "LEDG16") (pin "2") (pinfunction "K_2") (pintype "unspecified"))
      (node (ref "LEDG27") (pin "2") (pinfunction "K_2") (pintype "unspecified"))
      (node (ref "LEDG38") (pin "2") (pinfunction "K_2") (pintype "unspecified"))
      (node (ref "LEDG49") (pin "2") (pinfunction "K_2") (pintype "unspecified"))
      (node (ref "LEDG5") (pin "2") (pinfunction "K_2") (pintype "unspecified"))
      (node (ref "LEDG56") (pin "1") (pinfunction "A_1") (pintype "unspecified"))
      (node (ref "LEDG57") (pin "1") (pinfunction "A_1") (pintype "unspecified"))
      (node (ref "LEDG58") (pin "1") (pinfunction "A_1") (pintype "unspecified"))
      (node (ref "LEDG59") (pin "1") (pinfunction "A_1") (pintype "unspecified"))
      (node (ref "LEDG60") (pin "1") (pinfunction "A_1") (pintype "unspecified"))
      (node (ref "LEDG61") (pin "1") (pinfunction "A_1") (pintype "unspecified"))
      (node (ref "LEDG62") (pin "1") (pinfunction "A_1") (pintype "unspecified"))
      (node (ref "LEDG63") (pin "1") (pinfunction "A_1") (pintype "unspecified"))
      (node (ref "LEDG64") (pin "1") (pinfunction "A_1") (pintype "unspecified"))
      (node (ref "LEDG65") (pin "1") (pinfunction "A_1") (pintype "unspecified"))
      (node (ref "LEDG66") (pin "1") (pinfunction "A_1") (pintype "unspecified"))
      (node (ref "LEDG72") (pin "2") (pinfunction "K_2") (pintype "unspecified"))
      (node (ref "LEDG83") (pin "2") (pinfunction "K_2") (pintype "unspecified"))
      (node (ref "LEDG94") (pin "2") (pinfunction "K_2") (pintype "unspecified"))
      (node (ref "U1") (pin "35") (pinfunction "SDIO_DATA2_35") (pintype "unspecified"))
    )
    (net (code "33") (name "P7") (class "Default")
      (node (ref "LEDG106") (pin "2") (pinfunction "K_2") (pintype "unspecified"))
      (node (ref "LEDG117") (pin "2") (pinfunction "K_2") (pintype "unspecified"))
      (node (ref "LEDG128") (pin "2") (pinfunction "K_2") (pintype "unspecified"))
      (node (ref "LEDG17") (pin "2") (pinfunction "K_2") (pintype "unspecified"))
      (node (ref "LEDG28") (pin "2") (pinfunction "K_2") (pintype "unspecified"))
      (node (ref "LEDG39") (pin "2") (pinfunction "K_2") (pintype "unspecified"))
      (node (ref "LEDG50") (pin "2") (pinfunction "K_2") (pintype "unspecified"))
      (node (ref "LEDG6") (pin "2") (pinfunction "K_2") (pintype "unspecified"))
      (node (ref "LEDG61") (pin "2") (pinfunction "K_2") (pintype "unspecified"))
      (node (ref "LEDG67") (pin "1") (pinfunction "A_1") (pintype "unspecified"))
      (node (ref "LEDG68") (pin "1") (pinfunction "A_1") (pintype "unspecified"))
      (node (ref "LEDG69") (pin "1") (pinfunction "A_1") (pintype "unspecified"))
      (node (ref "LEDG70") (pin "1") (pinfunction "A_1") (pintype "unspecified"))
      (node (ref "LEDG71") (pin "1") (pinfunction "A_1") (pintype "unspecified"))
      (node (ref "LEDG72") (pin "1") (pinfunction "A_1") (pintype "unspecified"))
      (node (ref "LEDG73") (pin "1") (pinfunction "A_1") (pintype "unspecified"))
      (node (ref "LEDG74") (pin "1") (pinfunction "A_1") (pintype "unspecified"))
      (node (ref "LEDG75") (pin "1") (pinfunction "A_1") (pintype "unspecified"))
      (node (ref "LEDG76") (pin "1") (pinfunction "A_1") (pintype "unspecified"))
      (node (ref "LEDG77") (pin "1") (pinfunction "A_1") (pintype "unspecified"))
      (node (ref "LEDG84") (pin "2") (pinfunction "K_2") (pintype "unspecified"))
      (node (ref "LEDG95") (pin "2") (pinfunction "K_2") (pintype "unspecified"))
      (node (ref "U1") (pin "36") (pinfunction "SDIO_DATA3_36") (pintype "unspecified"))
    )
    (net (code "34") (name "P8") (class "Default")
      (node (ref "LEDG107") (pin "2") (pinfunction "K_2") (pintype "unspecified"))
      (node (ref "LEDG118") (pin "2") (pinfunction "K_2") (pintype "unspecified"))
      (node (ref "LEDG129") (pin "2") (pinfunction "K_2") (pintype "unspecified"))
      (node (ref "LEDG18") (pin "2") (pinfunction "K_2") (pintype "unspecified"))
      (node (ref "LEDG29") (pin "2") (pinfunction "K_2") (pintype "unspecified"))
      (node (ref "LEDG40") (pin "2") (pinfunction "K_2") (pintype "unspecified"))
      (node (ref "LEDG51") (pin "2") (pinfunction "K_2") (pintype "unspecified"))
      (node (ref "LEDG62") (pin "2") (pinfunction "K_2") (pintype "unspecified"))
      (node (ref "LEDG7") (pin "2") (pinfunction "K_2") (pintype "unspecified"))
      (node (ref "LEDG73") (pin "2") (pinfunction "K_2") (pintype "unspecified"))
      (node (ref "LEDG78") (pin "1") (pinfunction "A_1") (pintype "unspecified"))
      (node (ref "LEDG79") (pin "1") (pinfunction "A_1") (pintype "unspecified"))
      (node (ref "LEDG80") (pin "1") (pinfunction "A_1") (pintype "unspecified"))
      (node (ref "LEDG81") (pin "1") (pinfunction "A_1") (pintype "unspecified"))
      (node (ref "LEDG82") (pin "1") (pinfunction "A_1") (pintype "unspecified"))
      (node (ref "LEDG83") (pin "1") (pinfunction "A_1") (pintype "unspecified"))
      (node (ref "LEDG84") (pin "1") (pinfunction "A_1") (pintype "unspecified"))
      (node (ref "LEDG85") (pin "1") (pinfunction "A_1") (pintype "unspecified"))
      (node (ref "LEDG86") (pin "1") (pinfunction "A_1") (pintype "unspecified"))
      (node (ref "LEDG87") (pin "1") (pinfunction "A_1") (pintype "unspecified"))
      (node (ref "LEDG88") (pin "1") (pinfunction "A_1") (pintype "unspecified"))
      (node (ref "LEDG96") (pin "2") (pinfunction "K_2") (pintype "unspecified"))
      (node (ref "U1") (pin "34") (pinfunction "SDIO_DATA1_34") (pintype "unspecified"))
    )
    (net (code "35") (name "P9") (class "Default")
      (node (ref "LEDG108") (pin "2") (pinfunction "K_2") (pintype "unspecified"))
      (node (ref "LEDG119") (pin "2") (pinfunction "K_2") (pintype "unspecified"))
      (node (ref "LEDG130") (pin "2") (pinfunction "K_2") (pintype "unspecified"))
      (node (ref "LEDG19") (pin "2") (pinfunction "K_2") (pintype "unspecified"))
      (node (ref "LEDG30") (pin "2") (pinfunction "K_2") (pintype "unspecified"))
      (node (ref "LEDG41") (pin "2") (pinfunction "K_2") (pintype "unspecified"))
      (node (ref "LEDG52") (pin "2") (pinfunction "K_2") (pintype "unspecified"))
      (node (ref "LEDG63") (pin "2") (pinfunction "K_2") (pintype "unspecified"))
      (node (ref "LEDG74") (pin "2") (pinfunction "K_2") (pintype "unspecified"))
      (node (ref "LEDG8") (pin "2") (pinfunction "K_2") (pintype "unspecified"))
      (node (ref "LEDG85") (pin "2") (pinfunction "K_2") (pintype "unspecified"))
      (node (ref "LEDG89") (pin "1") (pinfunction "A_1") (pintype "unspecified"))
      (node (ref "LEDG90") (pin "1") (pinfunction "A_1") (pintype "unspecified"))
      (node (ref "LEDG91") (pin "1") (pinfunction "A_1") (pintype "unspecified"))
      (node (ref "LEDG92") (pin "1") (pinfunction "A_1") (pintype "unspecified"))
      (node (ref "LEDG93") (pin "1") (pinfunction "A_1") (pintype "unspecified"))
      (node (ref "LEDG94") (pin "1") (pinfunction "A_1") (pintype "unspecified"))
      (node (ref "LEDG95") (pin "1") (pinfunction "A_1") (pintype "unspecified"))
      (node (ref "LEDG96") (pin "1") (pinfunction "A_1") (pintype "unspecified"))
      (node (ref "LEDG97") (pin "1") (pinfunction "A_1") (pintype "unspecified"))
      (node (ref "LEDG98") (pin "1") (pinfunction "A_1") (pintype "unspecified"))
      (node (ref "LEDG99") (pin "1") (pinfunction "A_1") (pintype "unspecified"))
      (node (ref "U1") (pin "13") (pinfunction "MTDO_13") (pintype "unspecified"))
    )
    (net (code "36") (name "P10") (class "Default")
      (node (ref "LEDG100") (pin "1") (pinfunction "A_1") (pintype "unspecified"))
      (node (ref "LEDG101") (pin "1") (pinfunction "A_1") (pintype "unspecified"))
      (node (ref "LEDG102") (pin "1") (pinfunction "A_1") (pintype "unspecified"))
      (node (ref "LEDG103") (pin "1") (pinfunction "A_1") (pintype "unspecified"))
      (node (ref "LEDG104") (pin "1") (pinfunction "A_1") (pintype "unspecified"))
      (node (ref "LEDG105") (pin "1") (pinfunction "A_1") (pintype "unspecified"))
      (node (ref "LEDG106") (pin "1") (pinfunction "A_1") (pintype "unspecified"))
      (node (ref "LEDG107") (pin "1") (pinfunction "A_1") (pintype "unspecified"))
      (node (ref "LEDG108") (pin "1") (pinfunction "A_1") (pintype "unspecified"))
      (node (ref "LEDG109") (pin "1") (pinfunction "A_1") (pintype "unspecified"))
      (node (ref "LEDG110") (pin "1") (pinfunction "A_1") (pintype "unspecified"))
      (node (ref "LEDG120") (pin "2") (pinfunction "K_2") (pintype "unspecified"))
      (node (ref "LEDG131") (pin "2") (pinfunction "K_2") (pintype "unspecified"))
      (node (ref "LEDG20") (pin "2") (pinfunction "K_2") (pintype "unspecified"))
      (node (ref "LEDG31") (pin "2") (pinfunction "K_2") (pintype "unspecified"))
      (node (ref "LEDG42") (pin "2") (pinfunction "K_2") (pintype "unspecified"))
      (node (ref "LEDG53") (pin "2") (pinfunction "K_2") (pintype "unspecified"))
      (node (ref "LEDG64") (pin "2") (pinfunction "K_2") (pintype "unspecified"))
      (node (ref "LEDG75") (pin "2") (pinfunction "K_2") (pintype "unspecified"))
      (node (ref "LEDG86") (pin "2") (pinfunction "K_2") (pintype "unspecified"))
      (node (ref "LEDG9") (pin "2") (pinfunction "K_2") (pintype "unspecified"))
      (node (ref "LEDG97") (pin "2") (pinfunction "K_2") (pintype "unspecified"))
      (node (ref "U1") (pin "10") (pinfunction "MTMS_10") (pintype "unspecified"))
    )
    (net (code "37") (name "P11") (class "Default")
      (node (ref "LEDG10") (pin "2") (pinfunction "K_2") (pintype "unspecified"))
      (node (ref "LEDG109") (pin "2") (pinfunction "K_2") (pintype "unspecified"))
      (node (ref "LEDG111") (pin "1") (pinfunction "A_1") (pintype "unspecified"))
      (node (ref "LEDG112") (pin "1") (pinfunction "A_1") (pintype "unspecified"))
      (node (ref "LEDG113") (pin "1") (pinfunction "A_1") (pintype "unspecified"))
      (node (ref "LEDG114") (pin "1") (pinfunction "A_1") (pintype "unspecified"))
      (node (ref "LEDG115") (pin "1") (pinfunction "A_1") (pintype "unspecified"))
      (node (ref "LEDG116") (pin "1") (pinfunction "A_1") (pintype "unspecified"))
      (node (ref "LEDG117") (pin "1") (pinfunction "A_1") (pintype "unspecified"))
      (node (ref "LEDG118") (pin "1") (pinfunction "A_1") (pintype "unspecified"))
      (node (ref "LEDG119") (pin "1") (pinfunction "A_1") (pintype "unspecified"))
      (node (ref "LEDG120") (pin "1") (pinfunction "A_1") (pintype "unspecified"))
      (node (ref "LEDG121") (pin "1") (pinfunction "A_1") (pintype "unspecified"))
      (node (ref "LEDG132") (pin "2") (pinfunction "K_2") (pintype "unspecified"))
      (node (ref "LEDG21") (pin "2") (pinfunction "K_2") (pintype "unspecified"))
      (node (ref "LEDG32") (pin "2") (pinfunction "K_2") (pintype "unspecified"))
      (node (ref "LEDG43") (pin "2") (pinfunction "K_2") (pintype "unspecified"))
      (node (ref "LEDG54") (pin "2") (pinfunction "K_2") (pintype "unspecified"))
      (node (ref "LEDG65") (pin "2") (pinfunction "K_2") (pintype "unspecified"))
      (node (ref "LEDG76") (pin "2") (pinfunction "K_2") (pintype "unspecified"))
      (node (ref "LEDG87") (pin "2") (pinfunction "K_2") (pintype "unspecified"))
      (node (ref "LEDG98") (pin "2") (pinfunction "K_2") (pintype "unspecified"))
      (node (ref "U1") (pin "9") (pinfunction "GPIO3_9") (pintype "unspecified"))
    )
    (net (code "38") (name "P12") (class "Default")
      (node (ref "LEDG11") (pin "2") (pinfunction "K_2") (pintype "unspecified"))
      (node (ref "LEDG110") (pin "2") (pinfunction "K_2") (pintype "unspecified"))
      (node (ref "LEDG121") (pin "2") (pinfunction "K_2") (pintype "unspecified"))
      (node (ref "LEDG122") (pin "1") (pinfunction "A_1") (pintype "unspecified"))
      (node (ref "LEDG123") (pin "1") (pinfunction "A_1") (pintype "unspecified"))
      (node (ref "LEDG124") (pin "1") (pinfunction "A_1") (pintype "unspecified"))
      (node (ref "LEDG125") (pin "1") (pinfunction "A_1") (pintype "unspecified"))
      (node (ref "LEDG126") (pin "1") (pinfunction "A_1") (pintype "unspecified"))
      (node (ref "LEDG127") (pin "1") (pinfunction "A_1") (pintype "unspecified"))
      (node (ref "LEDG128") (pin "1") (pinfunction "A_1") (pintype "unspecified"))
      (node (ref "LEDG129") (pin "1") (pinfunction "A_1") (pintype "unspecified"))
      (node (ref "LEDG130") (pin "1") (pinfunction "A_1") (pintype "unspecified"))
      (node (ref "LEDG131") (pin "1") (pinfunction "A_1") (pintype "unspecified"))
      (node (ref "LEDG132") (pin "1") (pinfunction "A_1") (pintype "unspecified"))
      (node (ref "LEDG22") (pin "2") (pinfunction "K_2") (pintype "unspecified"))
      (node (ref "LEDG33") (pin "2") (pinfunction "K_2") (pintype "unspecified"))
      (node (ref "LEDG44") (pin "2") (pinfunction "K_2") (pintype "unspecified"))
      (node (ref "LEDG55") (pin "2") (pinfunction "K_2") (pintype "unspecified"))
      (node (ref "LEDG66") (pin "2") (pinfunction "K_2") (pintype "unspecified"))
      (node (ref "LEDG77") (pin "2") (pinfunction "K_2") (pintype "unspecified"))
      (node (ref "LEDG88") (pin "2") (pinfunction "K_2") (pintype "unspecified"))
      (node (ref "LEDG99") (pin "2") (pinfunction "K_2") (pintype "unspecified"))
      (node (ref "U8") (pin "4") (pinfunction "NO_2_4") (pintype "unspecified"))
    )
    (net (code "39") (name "P12_STRAP") (class "Default")
      (node (ref "U1") (pin "27") (pinfunction "GPIO15_27") (pintype "unspecified"))
      (node (ref "U8") (pin "6") (pinfunction "COM2_6") (pintype "unspecified"))
    )
    (net (code "40") (name "PWR_BTN") (class "Default")
      (node (ref "D1") (pin "2") (pinfunction "A_2") (pintype "unspecified"))
      (node (ref "D5") (pin "2") (pinfunction "A_2") (pintype "unspecified"))
      (node (ref "Q2") (pin "1") (pinfunction "G_1") (pintype "unspecified"))
      (node (ref "R28") (pin "2") (pinfunction "2_2") (pintype "input"))
      (node (ref "SW1") (pin "1") (pinfunction "1_1") (pintype "unspecified"))
      (node (ref "SW1") (pin "3") (pinfunction "3_3") (pintype "unspecified"))
      (node (ref "SW1") (pin "4") (pinfunction "4_4") (pintype "unspecified"))
    )
    (net (code "41") (name "PWR_CTRL") (class "Default")
      (node (ref "D4") (pin "2") (pinfunction "A_2") (pintype "unspecified"))
      (node (ref "R13") (pin "2") (pinfunction "2_2") (pintype "input"))
      (node (ref "TP1") (pin "1") (pinfunction "1_1") (pintype "unspecified"))
      (node (ref "U1") (pin "30") (pinfunction "U0RXD_30") (pintype "unspecified"))
    )
    (net (code "42") (name "RTC_CLKOUT") (class "Default")
      (node (ref "R22") (pin "2") (pinfunction "2_2") (pintype "input"))
      (node (ref "U15") (pin "1") (pinfunction "CLKOUT_1") (pintype "unspecified"))
    )
    (net (code "43") (name "RTC_INT#") (class "Default")
      (node (ref "R23") (pin "2") (pinfunction "2_2") (pintype "input"))
      (node (ref "U15") (pin "2") (pinfunction "INT#_2") (pintype "unspecified"))
    )
    (net (code "44") (name "SPICLK") (class "Default")
      (node (ref "U1") (pin "25") (pinfunction "SPICLK_25") (pintype "unspecified"))
      (node (ref "U2") (pin "6") (pinfunction "CLK_6") (pintype "unspecified"))
    )
    (net (code "45") (name "SPICS0") (class "Default")
      (node (ref "U1") (pin "20") (pinfunction "SPICS0_20") (pintype "unspecified"))
      (node (ref "U2") (pin "1") (pinfunction "CS#_1") (pintype "unspecified"))
    )
    (net (code "46") (name "SPID") (class "Default")
      (node (ref "U1") (pin "26") (pinfunction "SPID_26") (pintype "unspecified"))
      (node (ref "U2") (pin "5") (pinfunction "DI(IO0)_5") (pintype "unspecified"))
    )
    (net (code "47") (name "SPIHD") (class "Default")
      (node (ref "U1") (pin "24") (pinfunction "SPIHD_24") (pintype "unspecified"))
      (node (ref "U2") (pin "7") (pinfunction "HOLD#_or_RESET#(IO3)_7") (pintype "unspecified"))
    )
    (net (code "48") (name "SPIQ") (class "Default")
      (node (ref "U1") (pin "21") (pinfunction "SPIQ_21") (pintype "unspecified"))
      (node (ref "U2") (pin "2") (pinfunction "DO(IO1)_2") (pintype "unspecified"))
    )
    (net (code "49") (name "SPIWP") (class "Default")
      (node (ref "U1") (pin "22") (pinfunction "SPIWP_22") (pintype "unspecified"))
      (node (ref "U2") (pin "3") (pinfunction "WP#(IO2)_3") (pintype "unspecified"))
    )
    (net (code "50") (name "STRAP_CTRL") (class "Default")
      (node (ref "R27") (pin "2") (pinfunction "2_2") (pintype "input"))
      (node (ref "U1") (pin "7") (pinfunction "XTAL_32K_N_7") (pintype "unspecified"))
      (node (ref "U8") (pin "1") (pinfunction "IN_1_1") (pintype "unspecified"))
      (node (ref "U8") (pin "5") (pinfunction "IN_2_5") (pintype "unspecified"))
    )
    (net (code "51") (name "TXD") (class "Default")
      (node (ref "TP2") (pin "1") (pinfunction "1_1") (pintype "unspecified"))
      (node (ref "U1") (pin "29") (pinfunction "U0TXD_29") (pintype "unspecified"))
    )
    (net (code "52") (name "USB_5V") (class "Default")
      (node (ref "D2") (pin "2") (pinfunction "A_2") (pintype "unspecified"))
      (node (ref "D3") (pin "2") (pinfunction "A_2") (pintype "unspecified"))
      (node (ref "U4") (pin "4") (pinfunction "VDD_4") (pintype "unspecified"))
      (node (ref "U7") (pin "2") (pinfunction "A_2") (pintype "unspecified"))
      (node (ref "USB1") (pin "A4") (pinfunction "VBUS_A4") (pintype "unspecified"))
      (node (ref "USB1") (pin "A9") (pinfunction "VBUS_A9") (pintype "unspecified"))
    )
    (net (code "53") (name "USB_D_MINUS") (class "Default")
      (node (ref "R3") (pin "2") (pinfunction "2_2") (pintype "input"))
      (node (ref "USB1") (pin "A7") (pinfunction "DN1_A7") (pintype "unspecified"))
      (node (ref "USB1") (pin "B7") (pinfunction "DN2_B7") (pintype "unspecified"))
    )
    (net (code "54") (name "USB_D_PLUS") (class "Default")
      (node (ref "R4") (pin "2") (pinfunction "2_2") (pintype "input"))
      (node (ref "USB1") (pin "A6") (pinfunction "DP1_A6") (pintype "unspecified"))
      (node (ref "USB1") (pin "B6") (pinfunction "DP2_B6") (pintype "unspecified"))
    )
    (net (code "55") (name "VBAT") (class "Default")
      (node (ref "C11") (pin "2") (pinfunction "2_2") (pintype "unspecified"))
      (node (ref "C16") (pin "2") (pinfunction "2_2") (pintype "unspecified"))
      (node (ref "CN1") (pin "1") (pinfunction "1_1") (pintype "unspecified"))
      (node (ref "Q1") (pin "3") (pinfunction "D_3") (pintype "unspecified"))
      (node (ref "R12") (pin "2") (pinfunction "2_2") (pintype "input"))
      (node (ref "SW1") (pin "2") (pinfunction "2_2") (pintype "unspecified"))
      (node (ref "TP8") (pin "1") (pinfunction "1_1") (pintype "unspecified"))
      (node (ref "U15") (pin "6") (pinfunction "VBACKUP_6") (pintype "unspecified"))
      (node (ref "U4") (pin "3") (pinfunction "VBAT_3") (pintype "unspecified"))
    )
    (net (code "56") (name "VDD_SPI") (class "Default")
      (node (ref "C3") (pin "2") (pinfunction "2_2") (pintype "unspecified"))
      (node (ref "U1") (pin "23") (pinfunction "VDD_SPI_23") (pintype "unspecified"))
      (node (ref "U2") (pin "8") (pinfunction "VCC_8") (pintype "unspecified"))
    )
    (net (code "57") (name "VSENSE") (class "Default")
      (node (ref "C17") (pin "2") (pinfunction "2_2") (pintype "input"))
      (node (ref "R10") (pin "2") (pinfunction "2_2") (pintype "input"))
      (node (ref "R11") (pin "2") (pinfunction "2_2") (pintype "input"))
      (node (ref "R12") (pin "1") (pinfunction "1_1") (pintype "input"))
      (node (ref "U1") (pin "8") (pinfunction "GPIO2_8") (pintype "unspecified"))
    )
    (net (code "58") (name "WAKE_INT#") (class "Default")
      (node (ref "D6") (pin "2") (pinfunction "A_2") (pintype "unspecified"))
      (node (ref "R23") (pin "1") (pinfunction "1_1") (pintype "input"))
      (node (ref "R24") (pin "1") (pinfunction "1_1") (pintype "input"))
      (node (ref "R25") (pin "1") (pinfunction "1_1") (pintype "input"))
      (node (ref "R26") (pin "2") (pinfunction "2_2") (pintype "input"))
      (node (ref "TP9") (pin "1") (pinfunction "1_1") (pintype "unspecified"))
      (node (ref "U1") (pin "11") (pinfunction "MTDI_11") (pintype "unspecified"))
    )
    (net (code "59") (name "XTAL_N") (class "Default")
      (node (ref "C8") (pin "2") (pinfunction "2_2") (pintype "input"))
      (node (ref "U1") (pin "38") (pinfunction "XTAL_N_38") (pintype "unspecified"))
      (node (ref "X1") (pin "3") (pinfunction "3_3") (pintype "input"))
    )
    (net (code "60") (name "XTAL_P") (class "Default")
      (node (ref "C7") (pin "2") (pinfunction "2_2") (pintype "input"))
      (node (ref "U1") (pin "39") (pinfunction "XTAL_P_39") (pintype "unspecified"))
      (node (ref "X1") (pin "1") (pinfunction "1_1") (pintype "input"))
    )
    (net (code "61") (name "unconnected-(U5-Pad2)") (class "Default")
      (node (ref "U5") (pin "2") (pinfunction "2_2") (pintype "unspecified+no_connect"))
    )
    (net (code "62") (name "unconnected-(U6-NC-Pad4)") (class "Default")
      (node (ref "U6") (pin "4") (pinfunction "NC_4") (pintype "unspecified+no_connect"))
    )
    (net (code "63") (name "unconnected-(U8-NC_1-Pad9)") (class "Default")
      (node (ref "U8") (pin "9") (pinfunction "NC_1_9") (pintype "unspecified+no_connect"))
    )
    (net (code "64") (name "unconnected-(U8-NC_2-Pad7)") (class "Default")
      (node (ref "U8") (pin "7") (pinfunction "NC_2_7") (pintype "unspecified+no_connect"))
    )
    (net (code "65") (name "unconnected-(U14-INT1-Pad4)") (class "Default")
      (node (ref "U14") (pin "4") (pinfunction "INT1_4") (pintype "unspecified+no_connect"))
    )
    (net (code "66") (name "unconnected-(U14-NC-Pad10)") (class "Default")
      (node (ref "U14") (pin "10") (pinfunction "NC_10") (pintype "unspecified+no_connect"))
    )
    (net (code "67") (name "unconnected-(U14-NC-Pad11)") (class "Default")
      (node (ref "U14") (pin "11") (pinfunction "NC_11") (pintype "unspecified+no_connect"))
    )
    (net (code "68") (name "unconnected-(U14-SCx-Pad3)") (class "Default")
      (node (ref "U14") (pin "3") (pinfunction "SCx_3") (pintype "unspecified+no_connect"))
    )
    (net (code "69") (name "unconnected-(U14-SDx-Pad2)") (class "Default")
      (node (ref "U14") (pin "2") (pinfunction "SDx_2") (pintype "unspecified+no_connect"))
    )
    (net (code "70") (name "unconnected-(USB1-SBU1-PadA8)") (class "Default")
      (node (ref "USB1") (pin "A8") (pinfunction "SBU1_A8") (pintype "unspecified+no_connect"))
    )
    (net (code "71") (name "unconnected-(USB1-SBU2-PadB8)") (class "Default")
      (node (ref "USB1") (pin "B8") (pinfunction "SBU2_B8") (pintype "unspecified+no_connect"))
    )
  )
)
